# v7-flex2811_long.net
KiCad netlist of a schematic drawn in EAGLE
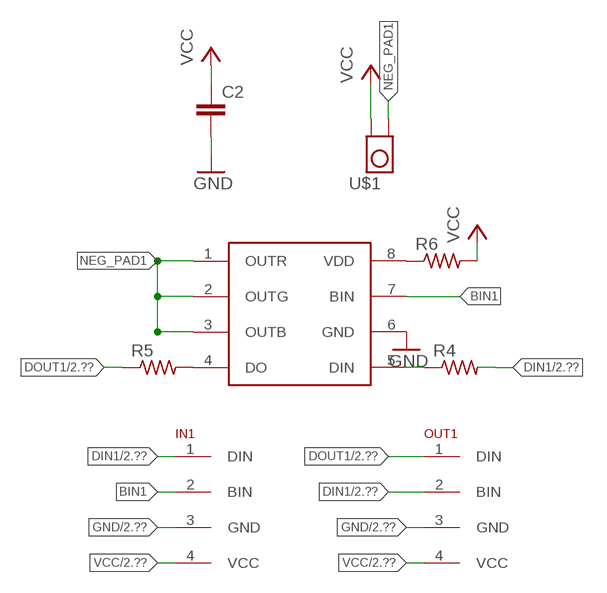
[diagram p0: schematic, sheet 1]
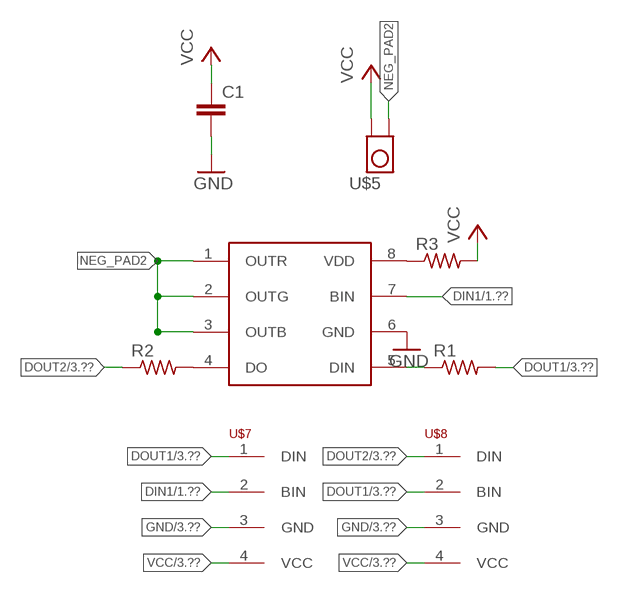
[diagram p1: schematic, sheet 2]
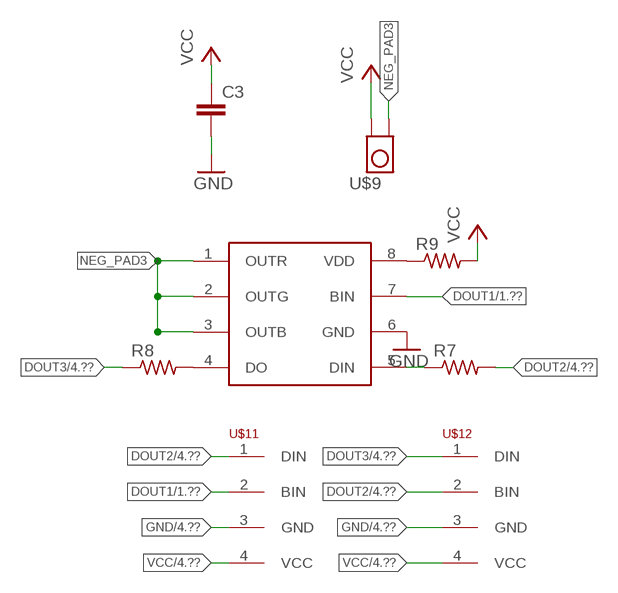
[diagram p2: schematic, sheet 3]
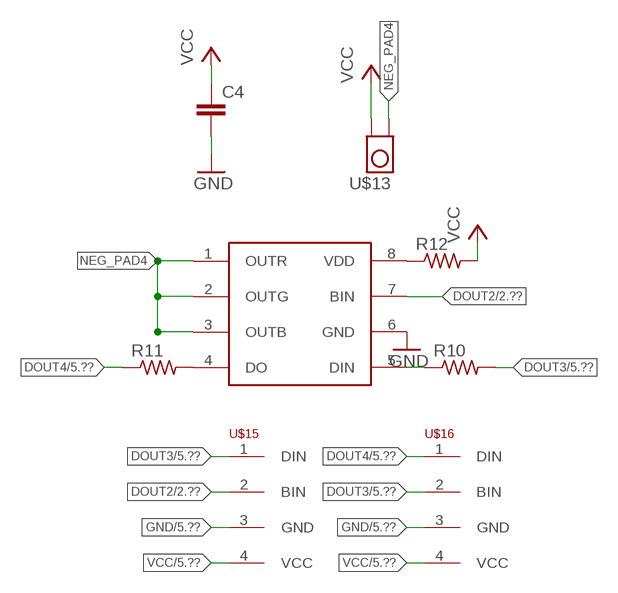
[diagram p3: schematic, sheet 4]
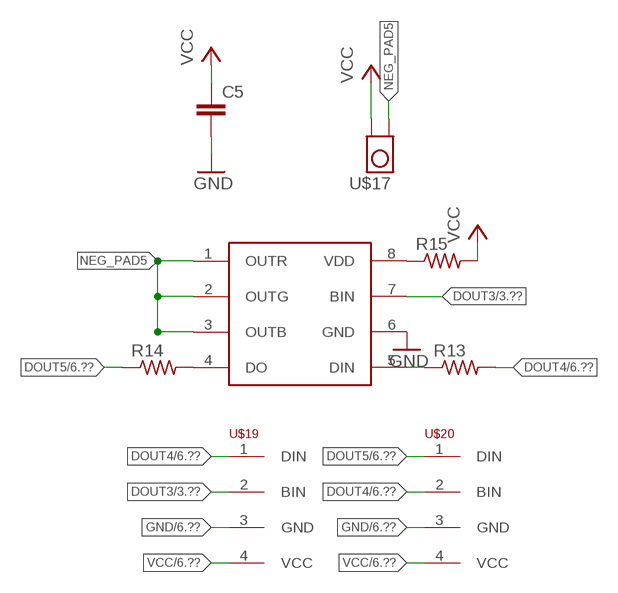
[diagram p4: schematic, sheet 5]
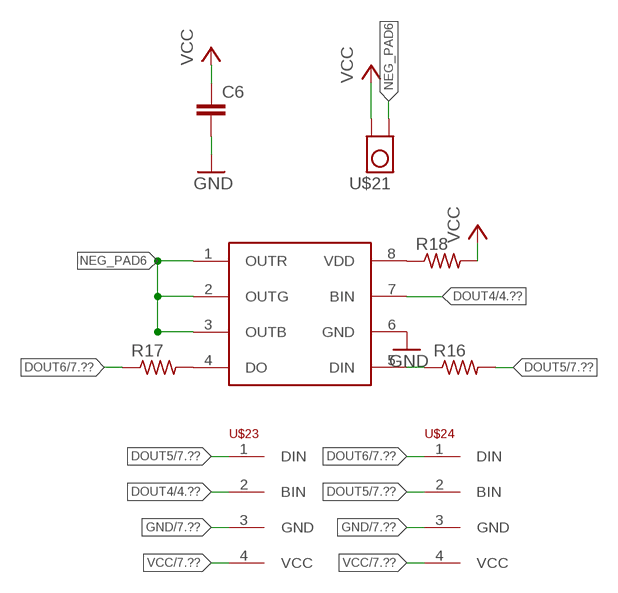
[diagram p5: schematic, sheet 6]
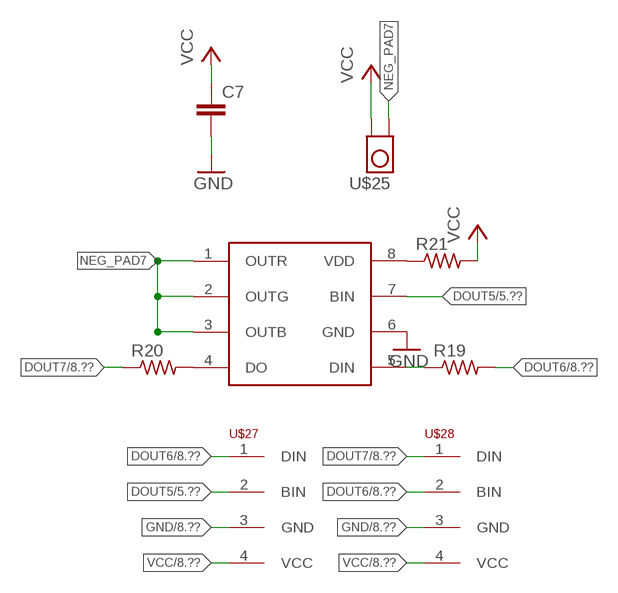
[diagram p6: schematic, sheet 7]
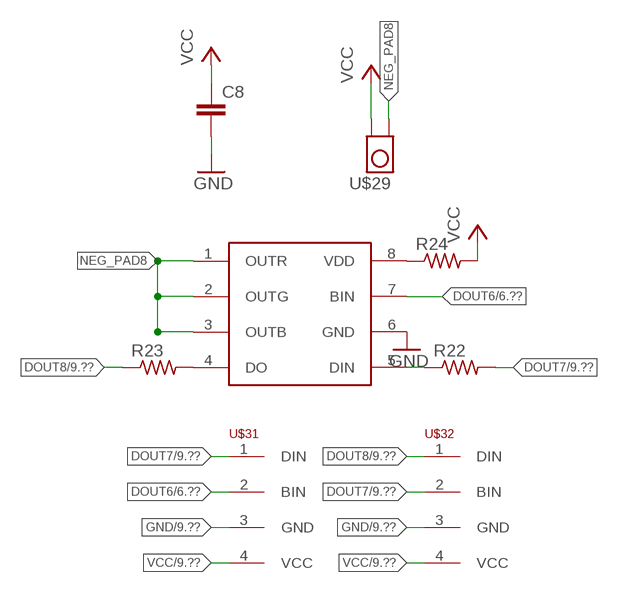
[diagram p7: schematic, sheet 8]
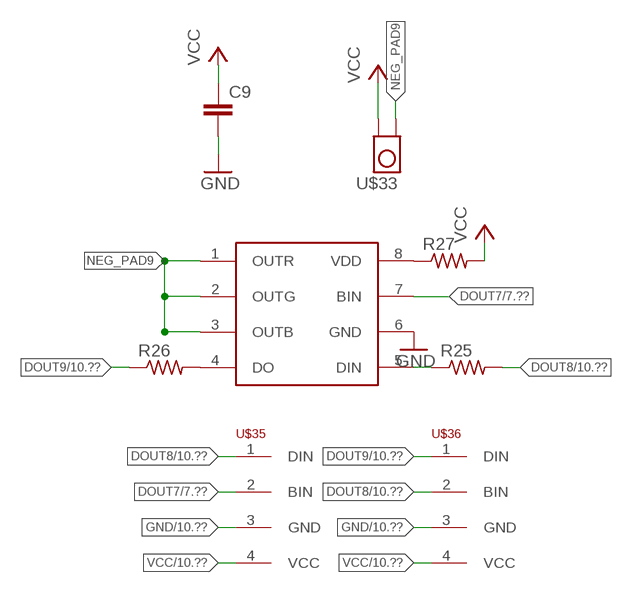
[diagram p8: schematic, sheet 9]
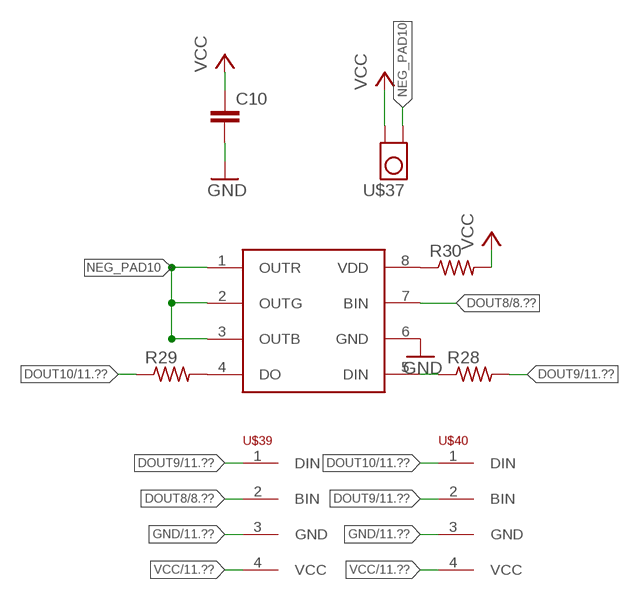
[diagram p9: schematic, sheet 10]
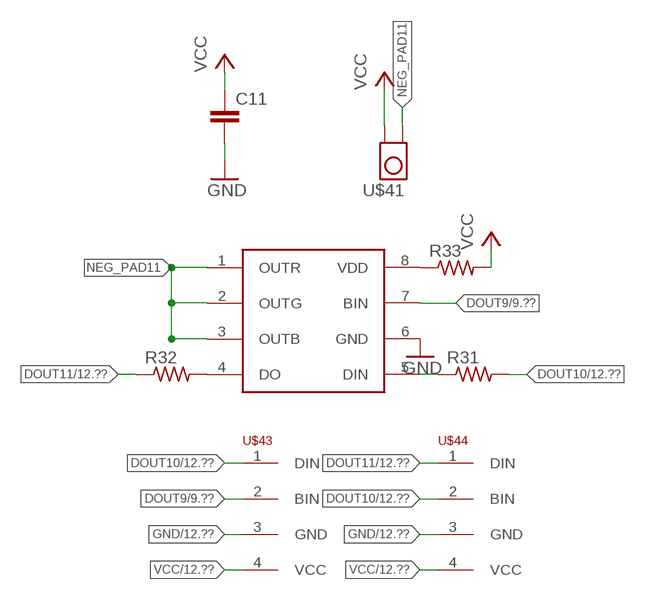
[diagram p10: schematic, sheet 11]
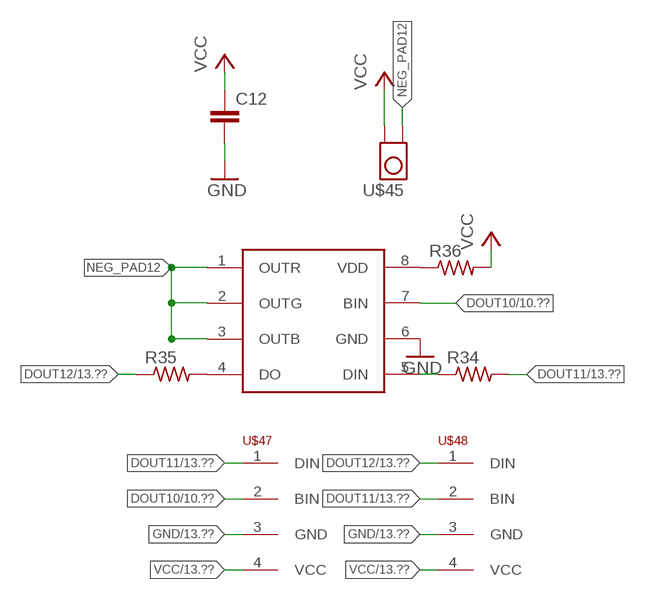
[diagram p11: schematic, sheet 12]
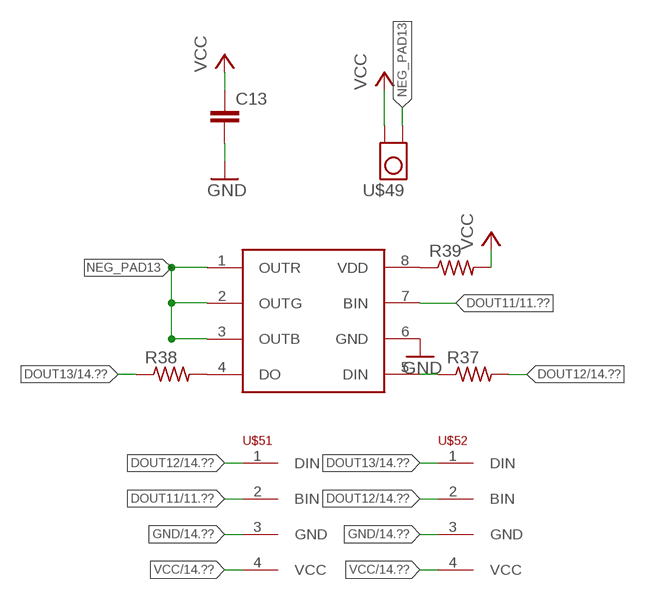
[diagram p12: schematic, sheet 13]
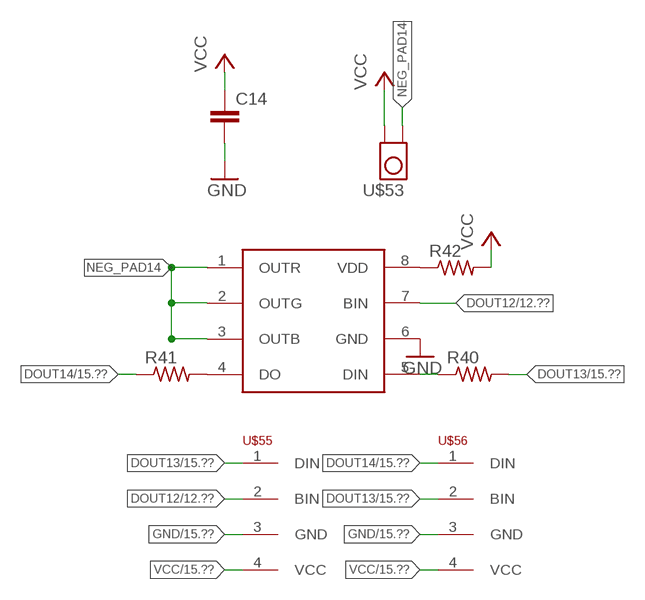
[diagram p13: schematic, sheet 14]
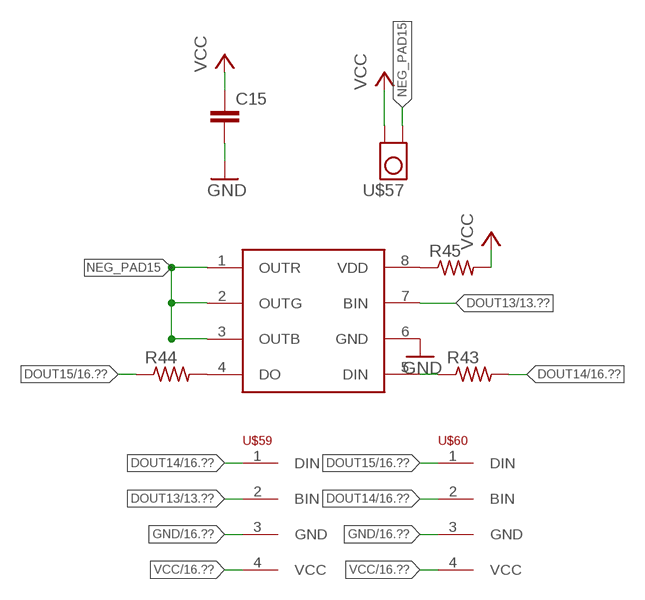
[diagram p14: schematic, sheet 15]
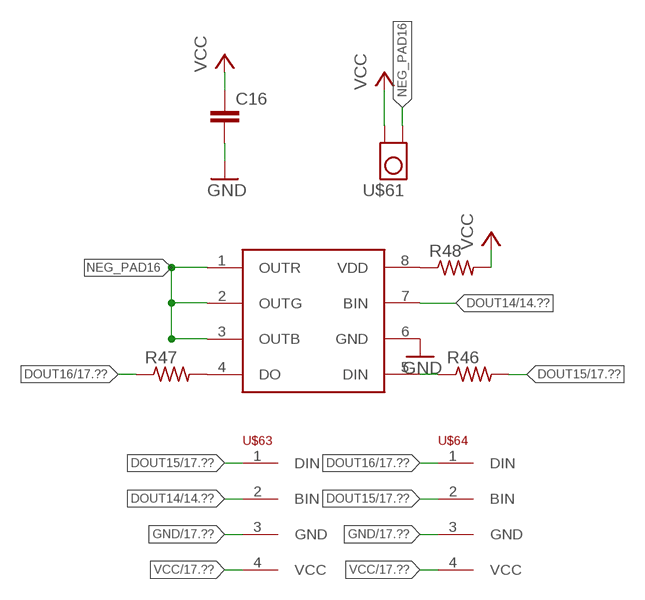
[diagram p15: schematic, sheet 16]
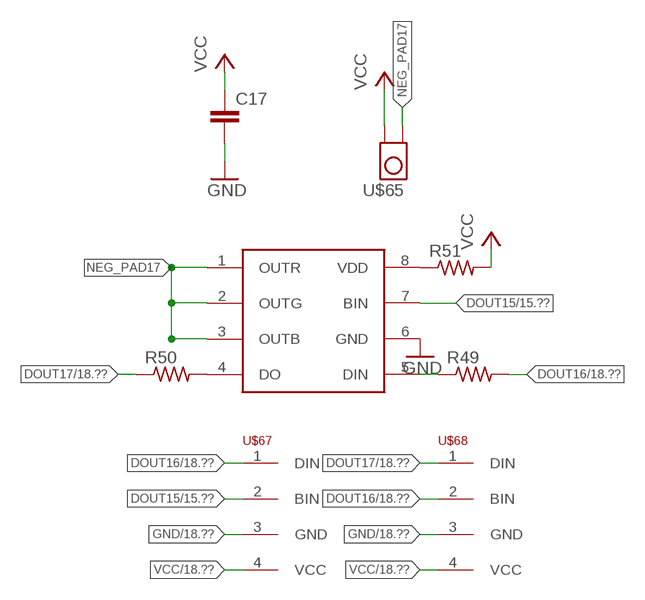
[diagram p16: schematic, sheet 17]
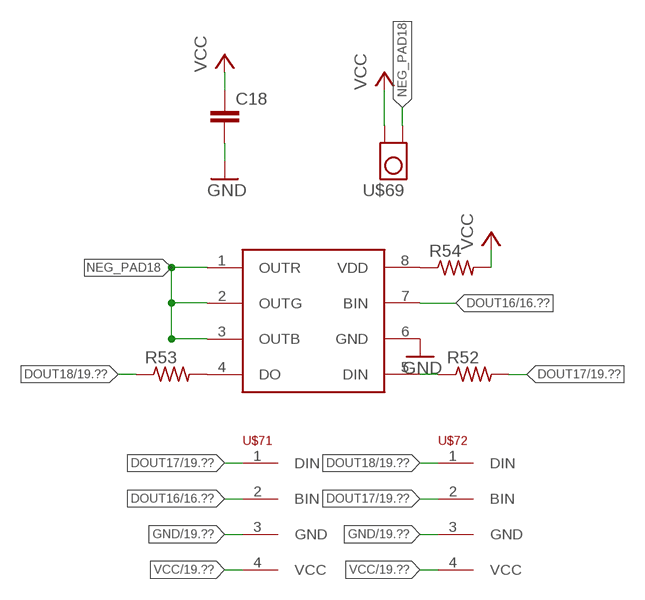
[diagram p17: schematic, sheet 18]
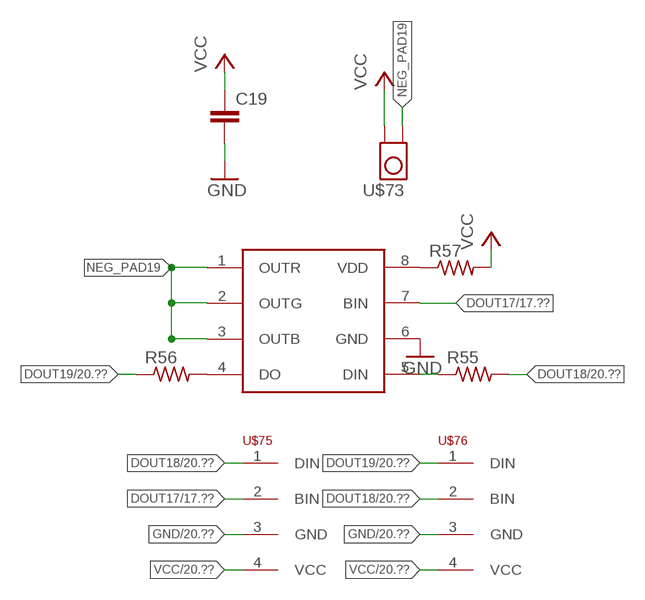
[diagram p18: schematic, sheet 19]
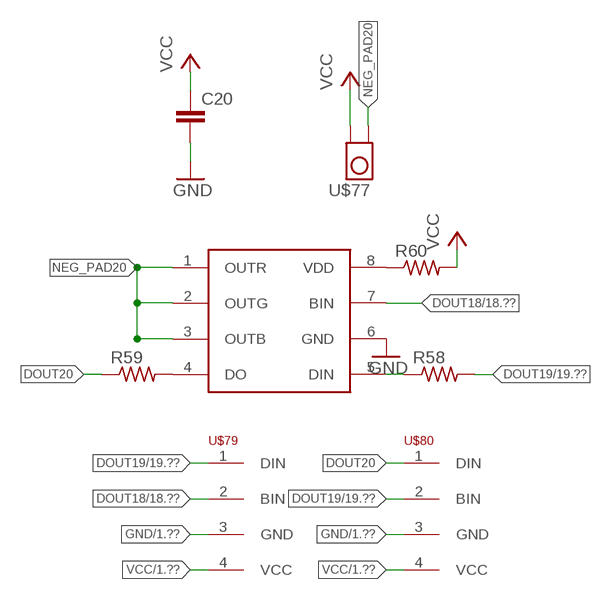
[diagram p19: schematic, sheet 20]

(export (version "E")
  (design (tool "Eeschema 10.0.6"))
  (components
    (comp (ref "C18")
      (value "C-EUC0201")
      (footprint "eagle-import:C0201")
      (libsource (lib "eagle-import") (part "C-EUC0201"))
    )
    (comp (ref "R52")
      (value "R-US_R0201")
      (footprint "eagle-import:R0201")
      (libsource (lib "eagle-import") (part "R-US_R0201"))
    )
    (comp (ref "R53")
      (value "R-US_R0201")
      (footprint "eagle-import:R0201")
      (libsource (lib "eagle-import") (part "R-US_R0201"))
    )
    (comp (ref "R54")
      (value "R-US_R0201")
      (footprint "eagle-import:R0201")
      (libsource (lib "eagle-import") (part "R-US_R0201"))
    )
    (comp (ref "U$69")
      (value "TP_4MM_MED_PAD")
      (footprint "eagle-import:TP_4MM_MED_PAD")
      (libsource (lib "eagle-import") (part "TP_4MM_MED_PAD"))
    )
    (comp (ref "U$70")
      (value "WS2818")
      (footprint "eagle-import:SO08")
      (libsource (lib "eagle-import") (part "WS2818"))
    )
    (comp (ref "U$71")
      (value "4PAD")
      (footprint "eagle-import:4PAD")
      (libsource (lib "eagle-import") (part "4PAD"))
    )
    (comp (ref "U$72")
      (value "4PAD")
      (footprint "eagle-import:4PAD")
      (libsource (lib "eagle-import") (part "4PAD"))
    )
    (comp (ref "C12")
      (value "C-EUC0201")
      (footprint "eagle-import:C0201")
      (libsource (lib "eagle-import") (part "C-EUC0201"))
    )
    (comp (ref "R34")
      (value "R-US_R0201")
      (footprint "eagle-import:R0201")
      (libsource (lib "eagle-import") (part "R-US_R0201"))
    )
    (comp (ref "R35")
      (value "R-US_R0201")
      (footprint "eagle-import:R0201")
      (libsource (lib "eagle-import") (part "R-US_R0201"))
    )
    (comp (ref "R36")
      (value "R-US_R0201")
      (footprint "eagle-import:R0201")
      (libsource (lib "eagle-import") (part "R-US_R0201"))
    )
    (comp (ref "U$45")
      (value "TP_4MM_MED_PAD")
      (footprint "eagle-import:TP_4MM_MED_PAD")
      (libsource (lib "eagle-import") (part "TP_4MM_MED_PAD"))
    )
    (comp (ref "U$46")
      (value "WS2818")
      (footprint "eagle-import:SO08")
      (libsource (lib "eagle-import") (part "WS2818"))
    )
    (comp (ref "U$47")
      (value "4PAD")
      (footprint "eagle-import:4PAD")
      (libsource (lib "eagle-import") (part "4PAD"))
    )
    (comp (ref "U$48")
      (value "4PAD")
      (footprint "eagle-import:4PAD")
      (libsource (lib "eagle-import") (part "4PAD"))
    )
    (comp (ref "C8")
      (value "C-EUC0201")
      (footprint "eagle-import:C0201")
      (libsource (lib "eagle-import") (part "C-EUC0201"))
    )
    (comp (ref "R22")
      (value "R-US_R0201")
      (footprint "eagle-import:R0201")
      (libsource (lib "eagle-import") (part "R-US_R0201"))
    )
    (comp (ref "R23")
      (value "R-US_R0201")
      (footprint "eagle-import:R0201")
      (libsource (lib "eagle-import") (part "R-US_R0201"))
    )
    (comp (ref "R24")
      (value "R-US_R0201")
      (footprint "eagle-import:R0201")
      (libsource (lib "eagle-import") (part "R-US_R0201"))
    )
    (comp (ref "U$29")
      (value "TP_4MM_MED_PAD")
      (footprint "eagle-import:TP_4MM_MED_PAD")
      (libsource (lib "eagle-import") (part "TP_4MM_MED_PAD"))
    )
    (comp (ref "U$30")
      (value "WS2818")
      (footprint "eagle-import:SO08")
      (libsource (lib "eagle-import") (part "WS2818"))
    )
    (comp (ref "U$31")
      (value "4PAD")
      (footprint "eagle-import:4PAD")
      (libsource (lib "eagle-import") (part "4PAD"))
    )
    (comp (ref "U$32")
      (value "4PAD")
      (footprint "eagle-import:4PAD")
      (libsource (lib "eagle-import") (part "4PAD"))
    )
    (comp (ref "C14")
      (value "C-EUC0201")
      (footprint "eagle-import:C0201")
      (libsource (lib "eagle-import") (part "C-EUC0201"))
    )
    (comp (ref "R40")
      (value "R-US_R0201")
      (footprint "eagle-import:R0201")
      (libsource (lib "eagle-import") (part "R-US_R0201"))
    )
    (comp (ref "R41")
      (value "R-US_R0201")
      (footprint "eagle-import:R0201")
      (libsource (lib "eagle-import") (part "R-US_R0201"))
    )
    (comp (ref "R42")
      (value "R-US_R0201")
      (footprint "eagle-import:R0201")
      (libsource (lib "eagle-import") (part "R-US_R0201"))
    )
    (comp (ref "U$53")
      (value "TP_4MM_MED_PAD")
      (footprint "eagle-import:TP_4MM_MED_PAD")
      (libsource (lib "eagle-import") (part "TP_4MM_MED_PAD"))
    )
    (comp (ref "U$54")
      (value "WS2818")
      (footprint "eagle-import:SO08")
      (libsource (lib "eagle-import") (part "WS2818"))
    )
    (comp (ref "U$55")
      (value "4PAD")
      (footprint "eagle-import:4PAD")
      (libsource (lib "eagle-import") (part "4PAD"))
    )
    (comp (ref "U$56")
      (value "4PAD")
      (footprint "eagle-import:4PAD")
      (libsource (lib "eagle-import") (part "4PAD"))
    )
    (comp (ref "C4")
      (value "C-EUC0201")
      (footprint "eagle-import:C0201")
      (libsource (lib "eagle-import") (part "C-EUC0201"))
    )
    (comp (ref "R10")
      (value "R-US_R0201")
      (footprint "eagle-import:R0201")
      (libsource (lib "eagle-import") (part "R-US_R0201"))
    )
    (comp (ref "R11")
      (value "R-US_R0201")
      (footprint "eagle-import:R0201")
      (libsource (lib "eagle-import") (part "R-US_R0201"))
    )
    (comp (ref "R12")
      (value "R-US_R0201")
      (footprint "eagle-import:R0201")
      (libsource (lib "eagle-import") (part "R-US_R0201"))
    )
    (comp (ref "U$13")
      (value "TP_4MM_MED_PAD")
      (footprint "eagle-import:TP_4MM_MED_PAD")
      (libsource (lib "eagle-import") (part "TP_4MM_MED_PAD"))
    )
    (comp (ref "U$14")
      (value "WS2818")
      (footprint "eagle-import:SO08")
      (libsource (lib "eagle-import") (part "WS2818"))
    )
    (comp (ref "U$15")
      (value "4PAD")
      (footprint "eagle-import:4PAD")
      (libsource (lib "eagle-import") (part "4PAD"))
    )
    (comp (ref "U$16")
      (value "4PAD")
      (footprint "eagle-import:4PAD")
      (libsource (lib "eagle-import") (part "4PAD"))
    )
    (comp (ref "C7")
      (value "C-EUC0201")
      (footprint "eagle-import:C0201")
      (libsource (lib "eagle-import") (part "C-EUC0201"))
    )
    (comp (ref "R19")
      (value "R-US_R0201")
      (footprint "eagle-import:R0201")
      (libsource (lib "eagle-import") (part "R-US_R0201"))
    )
    (comp (ref "R20")
      (value "R-US_R0201")
      (footprint "eagle-import:R0201")
      (libsource (lib "eagle-import") (part "R-US_R0201"))
    )
    (comp (ref "R21")
      (value "R-US_R0201")
      (footprint "eagle-import:R0201")
      (libsource (lib "eagle-import") (part "R-US_R0201"))
    )
    (comp (ref "U$25")
      (value "TP_4MM_MED_PAD")
      (footprint "eagle-import:TP_4MM_MED_PAD")
      (libsource (lib "eagle-import") (part "TP_4MM_MED_PAD"))
    )
    (comp (ref "U$26")
      (value "WS2818")
      (footprint "eagle-import:SO08")
      (libsource (lib "eagle-import") (part "WS2818"))
    )
    (comp (ref "U$27")
      (value "4PAD")
      (footprint "eagle-import:4PAD")
      (libsource (lib "eagle-import") (part "4PAD"))
    )
    (comp (ref "U$28")
      (value "4PAD")
      (footprint "eagle-import:4PAD")
      (libsource (lib "eagle-import") (part "4PAD"))
    )
    (comp (ref "C9")
      (value "C-EUC0201")
      (footprint "eagle-import:C0201")
      (libsource (lib "eagle-import") (part "C-EUC0201"))
    )
    (comp (ref "R25")
      (value "R-US_R0201")
      (footprint "eagle-import:R0201")
      (libsource (lib "eagle-import") (part "R-US_R0201"))
    )
    (comp (ref "R26")
      (value "R-US_R0201")
      (footprint "eagle-import:R0201")
      (libsource (lib "eagle-import") (part "R-US_R0201"))
    )
    (comp (ref "R27")
      (value "R-US_R0201")
      (footprint "eagle-import:R0201")
      (libsource (lib "eagle-import") (part "R-US_R0201"))
    )
    (comp (ref "U$33")
      (value "TP_4MM_MED_PAD")
      (footprint "eagle-import:TP_4MM_MED_PAD")
      (libsource (lib "eagle-import") (part "TP_4MM_MED_PAD"))
    )
    (comp (ref "U$34")
      (value "WS2818")
      (footprint "eagle-import:SO08")
      (libsource (lib "eagle-import") (part "WS2818"))
    )
    (comp (ref "U$35")
      (value "4PAD")
      (footprint "eagle-import:4PAD")
      (libsource (lib "eagle-import") (part "4PAD"))
    )
    (comp (ref "U$36")
      (value "4PAD")
      (footprint "eagle-import:4PAD")
      (libsource (lib "eagle-import") (part "4PAD"))
    )
    (comp (ref "C10")
      (value "C-EUC0201")
      (footprint "eagle-import:C0201")
      (libsource (lib "eagle-import") (part "C-EUC0201"))
    )
    (comp (ref "R28")
      (value "R-US_R0201")
      (footprint "eagle-import:R0201")
      (libsource (lib "eagle-import") (part "R-US_R0201"))
    )
    (comp (ref "R29")
      (value "R-US_R0201")
      (footprint "eagle-import:R0201")
      (libsource (lib "eagle-import") (part "R-US_R0201"))
    )
    (comp (ref "R30")
      (value "R-US_R0201")
      (footprint "eagle-import:R0201")
      (libsource (lib "eagle-import") (part "R-US_R0201"))
    )
    (comp (ref "U$37")
      (value "TP_4MM_MED_PAD")
      (footprint "eagle-import:TP_4MM_MED_PAD")
      (libsource (lib "eagle-import") (part "TP_4MM_MED_PAD"))
    )
    (comp (ref "U$38")
      (value "WS2818")
      (footprint "eagle-import:SO08")
      (libsource (lib "eagle-import") (part "WS2818"))
    )
    (comp (ref "U$39")
      (value "4PAD")
      (footprint "eagle-import:4PAD")
      (libsource (lib "eagle-import") (part "4PAD"))
    )
    (comp (ref "U$40")
      (value "4PAD")
      (footprint "eagle-import:4PAD")
      (libsource (lib "eagle-import") (part "4PAD"))
    )
    (comp (ref "C11")
      (value "C-EUC0201")
      (footprint "eagle-import:C0201")
      (libsource (lib "eagle-import") (part "C-EUC0201"))
    )
    (comp (ref "R31")
      (value "R-US_R0201")
      (footprint "eagle-import:R0201")
      (libsource (lib "eagle-import") (part "R-US_R0201"))
    )
    (comp (ref "R32")
      (value "R-US_R0201")
      (footprint "eagle-import:R0201")
      (libsource (lib "eagle-import") (part "R-US_R0201"))
    )
    (comp (ref "R33")
      (value "R-US_R0201")
      (footprint "eagle-import:R0201")
      (libsource (lib "eagle-import") (part "R-US_R0201"))
    )
    (comp (ref "U$41")
      (value "TP_4MM_MED_PAD")
      (footprint "eagle-import:TP_4MM_MED_PAD")
      (libsource (lib "eagle-import") (part "TP_4MM_MED_PAD"))
    )
    (comp (ref "U$42")
      (value "WS2818")
      (footprint "eagle-import:SO08")
      (libsource (lib "eagle-import") (part "WS2818"))
    )
    (comp (ref "U$43")
      (value "4PAD")
      (footprint "eagle-import:4PAD")
      (libsource (lib "eagle-import") (part "4PAD"))
    )
    (comp (ref "U$44")
      (value "4PAD")
      (footprint "eagle-import:4PAD")
      (libsource (lib "eagle-import") (part "4PAD"))
    )
    (comp (ref "C19")
      (value "C-EUC0201")
      (footprint "eagle-import:C0201")
      (libsource (lib "eagle-import") (part "C-EUC0201"))
    )
    (comp (ref "R55")
      (value "R-US_R0201")
      (footprint "eagle-import:R0201")
      (libsource (lib "eagle-import") (part "R-US_R0201"))
    )
    (comp (ref "R56")
      (value "R-US_R0201")
      (footprint "eagle-import:R0201")
      (libsource (lib "eagle-import") (part "R-US_R0201"))
    )
    (comp (ref "R57")
      (value "R-US_R0201")
      (footprint "eagle-import:R0201")
      (libsource (lib "eagle-import") (part "R-US_R0201"))
    )
    (comp (ref "U$73")
      (value "TP_4MM_MED_PAD")
      (footprint "eagle-import:TP_4MM_MED_PAD")
      (libsource (lib "eagle-import") (part "TP_4MM_MED_PAD"))
    )
    (comp (ref "U$74")
      (value "WS2818")
      (footprint "eagle-import:SO08")
      (libsource (lib "eagle-import") (part "WS2818"))
    )
    (comp (ref "U$75")
      (value "4PAD")
      (footprint "eagle-import:4PAD")
      (libsource (lib "eagle-import") (part "4PAD"))
    )
    (comp (ref "U$76")
      (value "4PAD")
      (footprint "eagle-import:4PAD")
      (libsource (lib "eagle-import") (part "4PAD"))
    )
    (comp (ref "C15")
      (value "C-EUC0201")
      (footprint "eagle-import:C0201")
      (libsource (lib "eagle-import") (part "C-EUC0201"))
    )
    (comp (ref "R43")
      (value "R-US_R0201")
      (footprint "eagle-import:R0201")
      (libsource (lib "eagle-import") (part "R-US_R0201"))
    )
    (comp (ref "R44")
      (value "R-US_R0201")
      (footprint "eagle-import:R0201")
      (libsource (lib "eagle-import") (part "R-US_R0201"))
    )
    (comp (ref "R45")
      (value "R-US_R0201")
      (footprint "eagle-import:R0201")
      (libsource (lib "eagle-import") (part "R-US_R0201"))
    )
    (comp (ref "U$57")
      (value "TP_4MM_MED_PAD")
      (footprint "eagle-import:TP_4MM_MED_PAD")
      (libsource (lib "eagle-import") (part "TP_4MM_MED_PAD"))
    )
    (comp (ref "U$58")
      (value "WS2818")
      (footprint "eagle-import:SO08")
      (libsource (lib "eagle-import") (part "WS2818"))
    )
    (comp (ref "U$59")
      (value "4PAD")
      (footprint "eagle-import:4PAD")
      (libsource (lib "eagle-import") (part "4PAD"))
    )
    (comp (ref "U$60")
      (value "4PAD")
      (footprint "eagle-import:4PAD")
      (libsource (lib "eagle-import") (part "4PAD"))
    )
    (comp (ref "C5")
      (value "C-EUC0201")
      (footprint "eagle-import:C0201")
      (libsource (lib "eagle-import") (part "C-EUC0201"))
    )
    (comp (ref "R13")
      (value "R-US_R0201")
      (footprint "eagle-import:R0201")
      (libsource (lib "eagle-import") (part "R-US_R0201"))
    )
    (comp (ref "R14")
      (value "R-US_R0201")
      (footprint "eagle-import:R0201")
      (libsource (lib "eagle-import") (part "R-US_R0201"))
    )
    (comp (ref "R15")
      (value "R-US_R0201")
      (footprint "eagle-import:R0201")
      (libsource (lib "eagle-import") (part "R-US_R0201"))
    )
    (comp (ref "U$17")
      (value "TP_4MM_MED_PAD")
      (footprint "eagle-import:TP_4MM_MED_PAD")
      (libsource (lib "eagle-import") (part "TP_4MM_MED_PAD"))
    )
    (comp (ref "U$18")
      (value "WS2818")
      (footprint "eagle-import:SO08")
      (libsource (lib "eagle-import") (part "WS2818"))
    )
    (comp (ref "U$19")
      (value "4PAD")
      (footprint "eagle-import:4PAD")
      (libsource (lib "eagle-import") (part "4PAD"))
    )
    (comp (ref "U$20")
      (value "4PAD")
      (footprint "eagle-import:4PAD")
      (libsource (lib "eagle-import") (part "4PAD"))
    )
    (comp (ref "C20")
      (value "C-EUC0201")
      (footprint "eagle-import:C0201")
      (libsource (lib "eagle-import") (part "C-EUC0201"))
    )
    (comp (ref "R58")
      (value "R-US_R0201")
      (footprint "eagle-import:R0201")
      (libsource (lib "eagle-import") (part "R-US_R0201"))
    )
    (comp (ref "R59")
      (value "R-US_R0201")
      (footprint "eagle-import:R0201")
      (libsource (lib "eagle-import") (part "R-US_R0201"))
    )
    (comp (ref "R60")
      (value "R-US_R0201")
      (footprint "eagle-import:R0201")
      (libsource (lib "eagle-import") (part "R-US_R0201"))
    )
    (comp (ref "U$77")
      (value "TP_4MM_MED_PAD")
      (footprint "eagle-import:TP_4MM_MED_PAD")
      (libsource (lib "eagle-import") (part "TP_4MM_MED_PAD"))
    )
    (comp (ref "U$78")
      (value "WS2818")
      (footprint "eagle-import:SO08")
      (libsource (lib "eagle-import") (part "WS2818"))
    )
    (comp (ref "U$79")
      (value "4PAD")
      (footprint "eagle-import:4PAD")
      (libsource (lib "eagle-import") (part "4PAD"))
    )
    (comp (ref "U$80")
      (value "4PAD")
      (footprint "eagle-import:4PAD")
      (libsource (lib "eagle-import") (part "4PAD"))
    )
    (comp (ref "C17")
      (value "C-EUC0201")
      (footprint "eagle-import:C0201")
      (libsource (lib "eagle-import") (part "C-EUC0201"))
    )
    (comp (ref "R49")
      (value "R-US_R0201")
      (footprint "eagle-import:R0201")
      (libsource (lib "eagle-import") (part "R-US_R0201"))
    )
    (comp (ref "R50")
      (value "R-US_R0201")
      (footprint "eagle-import:R0201")
      (libsource (lib "eagle-import") (part "R-US_R0201"))
    )
    (comp (ref "R51")
      (value "R-US_R0201")
      (footprint "eagle-import:R0201")
      (libsource (lib "eagle-import") (part "R-US_R0201"))
    )
    (comp (ref "U$65")
      (value "TP_4MM_MED_PAD")
      (footprint "eagle-import:TP_4MM_MED_PAD")
      (libsource (lib "eagle-import") (part "TP_4MM_MED_PAD"))
    )
    (comp (ref "U$66")
      (value "WS2818")
      (footprint "eagle-import:SO08")
      (libsource (lib "eagle-import") (part "WS2818"))
    )
    (comp (ref "U$67")
      (value "4PAD")
      (footprint "eagle-import:4PAD")
      (libsource (lib "eagle-import") (part "4PAD"))
    )
    (comp (ref "U$68")
      (value "4PAD")
      (footprint "eagle-import:4PAD")
      (libsource (lib "eagle-import") (part "4PAD"))
    )
    (comp (ref "C6")
      (value "C-EUC0201")
      (footprint "eagle-import:C0201")
      (libsource (lib "eagle-import") (part "C-EUC0201"))
    )
    (comp (ref "R16")
      (value "R-US_R0201")
      (footprint "eagle-import:R0201")
      (libsource (lib "eagle-import") (part "R-US_R0201"))
    )
    (comp (ref "R17")
      (value "R-US_R0201")
      (footprint "eagle-import:R0201")
      (libsource (lib "eagle-import") (part "R-US_R0201"))
    )
    (comp (ref "R18")
      (value "R-US_R0201")
      (footprint "eagle-import:R0201")
      (libsource (lib "eagle-import") (part "R-US_R0201"))
    )
    (comp (ref "U$21")
      (value "TP_4MM_MED_PAD")
      (footprint "eagle-import:TP_4MM_MED_PAD")
      (libsource (lib "eagle-import") (part "TP_4MM_MED_PAD"))
    )
    (comp (ref "U$22")
      (value "WS2818")
      (footprint "eagle-import:SO08")
      (libsource (lib "eagle-import") (part "WS2818"))
    )
    (comp (ref "U$23")
      (value "4PAD")
      (footprint "eagle-import:4PAD")
      (libsource (lib "eagle-import") (part "4PAD"))
    )
    (comp (ref "U$24")
      (value "4PAD")
      (footprint "eagle-import:4PAD")
      (libsource (lib "eagle-import") (part "4PAD"))
    )
    (comp (ref "C2")
      (value "C-EUC0201")
      (footprint "eagle-import:C0201")
      (libsource (lib "eagle-import") (part "C-EUC0201"))
    )
    (comp (ref "IN1")
      (value "4PAD")
      (footprint "eagle-import:4PAD")
      (libsource (lib "eagle-import") (part "4PAD"))
    )
    (comp (ref "OUT1")
      (value "4PAD")
      (footprint "eagle-import:4PAD")
      (libsource (lib "eagle-import") (part "4PAD"))
    )
    (comp (ref "R4")
      (value "R-US_R0201")
      (footprint "eagle-import:R0201")
      (libsource (lib "eagle-import") (part "R-US_R0201"))
    )
    (comp (ref "R5")
      (value "R-US_R0201")
      (footprint "eagle-import:R0201")
      (libsource (lib "eagle-import") (part "R-US_R0201"))
    )
    (comp (ref "R6")
      (value "R-US_R0201")
      (footprint "eagle-import:R0201")
      (libsource (lib "eagle-import") (part "R-US_R0201"))
    )
    (comp (ref "U$1")
      (value "TP_4MM_MED_PAD")
      (footprint "eagle-import:TP_4MM_MED_PAD")
      (libsource (lib "eagle-import") (part "TP_4MM_MED_PAD"))
    )
    (comp (ref "U$2")
      (value "WS2818")
      (footprint "eagle-import:SO08")
      (libsource (lib "eagle-import") (part "WS2818"))
    )
    (comp (ref "C13")
      (value "C-EUC0201")
      (footprint "eagle-import:C0201")
      (libsource (lib "eagle-import") (part "C-EUC0201"))
    )
    (comp (ref "R37")
      (value "R-US_R0201")
      (footprint "eagle-import:R0201")
      (libsource (lib "eagle-import") (part "R-US_R0201"))
    )
    (comp (ref "R38")
      (value "R-US_R0201")
      (footprint "eagle-import:R0201")
      (libsource (lib "eagle-import") (part "R-US_R0201"))
    )
    (comp (ref "R39")
      (value "R-US_R0201")
      (footprint "eagle-import:R0201")
      (libsource (lib "eagle-import") (part "R-US_R0201"))
    )
    (comp (ref "U$49")
      (value "TP_4MM_MED_PAD")
      (footprint "eagle-import:TP_4MM_MED_PAD")
      (libsource (lib "eagle-import") (part "TP_4MM_MED_PAD"))
    )
    (comp (ref "U$50")
      (value "WS2818")
      (footprint "eagle-import:SO08")
      (libsource (lib "eagle-import") (part "WS2818"))
    )
    (comp (ref "U$51")
      (value "4PAD")
      (footprint "eagle-import:4PAD")
      (libsource (lib "eagle-import") (part "4PAD"))
    )
    (comp (ref "U$52")
      (value "4PAD")
      (footprint "eagle-import:4PAD")
      (libsource (lib "eagle-import") (part "4PAD"))
    )
    (comp (ref "C16")
      (value "C-EUC0201")
      (footprint "eagle-import:C0201")
      (libsource (lib "eagle-import") (part "C-EUC0201"))
    )
    (comp (ref "R46")
      (value "R-US_R0201")
      (footprint "eagle-import:R0201")
      (libsource (lib "eagle-import") (part "R-US_R0201"))
    )
    (comp (ref "R47")
      (value "R-US_R0201")
      (footprint "eagle-import:R0201")
      (libsource (lib "eagle-import") (part "R-US_R0201"))
    )
    (comp (ref "R48")
      (value "R-US_R0201")
      (footprint "eagle-import:R0201")
      (libsource (lib "eagle-import") (part "R-US_R0201"))
    )
    (comp (ref "U$61")
      (value "TP_4MM_MED_PAD")
      (footprint "eagle-import:TP_4MM_MED_PAD")
      (libsource (lib "eagle-import") (part "TP_4MM_MED_PAD"))
    )
    (comp (ref "U$62")
      (value "WS2818")
      (footprint "eagle-import:SO08")
      (libsource (lib "eagle-import") (part "WS2818"))
    )
    (comp (ref "U$63")
      (value "4PAD")
      (footprint "eagle-import:4PAD")
      (libsource (lib "eagle-import") (part "4PAD"))
    )
    (comp (ref "U$64")
      (value "4PAD")
      (footprint "eagle-import:4PAD")
      (libsource (lib "eagle-import") (part "4PAD"))
    )
    (comp (ref "C3")
      (value "C-EUC0201")
      (footprint "eagle-import:C0201")
      (libsource (lib "eagle-import") (part "C-EUC0201"))
    )
    (comp (ref "R7")
      (value "R-US_R0201")
      (footprint "eagle-import:R0201")
      (libsource (lib "eagle-import") (part "R-US_R0201"))
    )
    (comp (ref "R8")
      (value "R-US_R0201")
      (footprint "eagle-import:R0201")
      (libsource (lib "eagle-import") (part "R-US_R0201"))
    )
    (comp (ref "R9")
      (value "R-US_R0201")
      (footprint "eagle-import:R0201")
      (libsource (lib "eagle-import") (part "R-US_R0201"))
    )
    (comp (ref "U$9")
      (value "TP_4MM_MED_PAD")
      (footprint "eagle-import:TP_4MM_MED_PAD")
      (libsource (lib "eagle-import") (part "TP_4MM_MED_PAD"))
    )
    (comp (ref "U$10")
      (value "WS2818")
      (footprint "eagle-import:SO08")
      (libsource (lib "eagle-import") (part "WS2818"))
    )
    (comp (ref "U$11")
      (value "4PAD")
      (footprint "eagle-import:4PAD")
      (libsource (lib "eagle-import") (part "4PAD"))
    )
    (comp (ref "U$12")
      (value "4PAD")
      (footprint "eagle-import:4PAD")
      (libsource (lib "eagle-import") (part "4PAD"))
    )
    (comp (ref "C1")
      (value "C-EUC0201")
      (footprint "eagle-import:C0201")
      (libsource (lib "eagle-import") (part "C-EUC0201"))
    )
    (comp (ref "R1")
      (value "R-US_R0201")
      (footprint "eagle-import:R0201")
      (libsource (lib "eagle-import") (part "R-US_R0201"))
    )
    (comp (ref "R2")
      (value "R-US_R0201")
      (footprint "eagle-import:R0201")
      (libsource (lib "eagle-import") (part "R-US_R0201"))
    )
    (comp (ref "R3")
      (value "R-US_R0201")
      (footprint "eagle-import:R0201")
      (libsource (lib "eagle-import") (part "R-US_R0201"))
    )
    (comp (ref "U$5")
      (value "TP_4MM_MED_PAD")
      (footprint "eagle-import:TP_4MM_MED_PAD")
      (libsource (lib "eagle-import") (part "TP_4MM_MED_PAD"))
    )
    (comp (ref "U$6")
      (value "WS2818")
      (footprint "eagle-import:SO08")
      (libsource (lib "eagle-import") (part "WS2818"))
    )
    (comp (ref "U$7")
      (value "4PAD")
      (footprint "eagle-import:4PAD")
      (libsource (lib "eagle-import") (part "4PAD"))
    )
    (comp (ref "U$8")
      (value "4PAD")
      (footprint "eagle-import:4PAD")
      (libsource (lib "eagle-import") (part "4PAD"))
    )
  )
  (nets
    (net (code "1") (name "BIN1") (class "Default")
      (node (ref "IN1") (pin "2") (pinfunction "BIN_2") (pintype "bidirectional"))
      (node (ref "U$2") (pin "7") (pinfunction "BIN_7") (pintype "bidirectional"))
    )
    (net (code "2") (name "DIN1") (class "Default")
      (node (ref "IN1") (pin "1") (pinfunction "DIN_1") (pintype "bidirectional"))
      (node (ref "OUT1") (pin "2") (pinfunction "BIN_2") (pintype "bidirectional"))
      (node (ref "R4") (pin "2") (pinfunction "2_2") (pintype "passive"))
      (node (ref "U$6") (pin "7") (pinfunction "BIN_7") (pintype "bidirectional"))
      (node (ref "U$7") (pin "2") (pinfunction "BIN_2") (pintype "bidirectional"))
    )
    (net (code "3") (name "DOUT1") (class "Default")
      (node (ref "OUT1") (pin "1") (pinfunction "DIN_1") (pintype "bidirectional"))
      (node (ref "R1") (pin "2") (pinfunction "2_2") (pintype "passive"))
      (node (ref "R5") (pin "1") (pinfunction "1_1") (pintype "passive"))
      (node (ref "U$10") (pin "7") (pinfunction "BIN_7") (pintype "bidirectional"))
      (node (ref "U$11") (pin "2") (pinfunction "BIN_2") (pintype "bidirectional"))
      (node (ref "U$7") (pin "1") (pinfunction "DIN_1") (pintype "bidirectional"))
      (node (ref "U$8") (pin "2") (pinfunction "BIN_2") (pintype "bidirectional"))
    )
    (net (code "4") (name "DOUT2") (class "Default")
      (node (ref "R2") (pin "1") (pinfunction "1_1") (pintype "passive"))
      (node (ref "R7") (pin "2") (pinfunction "2_2") (pintype "passive"))
      (node (ref "U$11") (pin "1") (pinfunction "DIN_1") (pintype "bidirectional"))
      (node (ref "U$12") (pin "2") (pinfunction "BIN_2") (pintype "bidirectional"))
      (node (ref "U$14") (pin "7") (pinfunction "BIN_7") (pintype "bidirectional"))
      (node (ref "U$15") (pin "2") (pinfunction "BIN_2") (pintype "bidirectional"))
      (node (ref "U$8") (pin "1") (pinfunction "DIN_1") (pintype "bidirectional"))
    )
    (net (code "5") (name "DOUT3") (class "Default")
      (node (ref "R10") (pin "2") (pinfunction "2_2") (pintype "passive"))
      (node (ref "R8") (pin "1") (pinfunction "1_1") (pintype "passive"))
      (node (ref "U$12") (pin "1") (pinfunction "DIN_1") (pintype "bidirectional"))
      (node (ref "U$15") (pin "1") (pinfunction "DIN_1") (pintype "bidirectional"))
      (node (ref "U$16") (pin "2") (pinfunction "BIN_2") (pintype "bidirectional"))
      (node (ref "U$18") (pin "7") (pinfunction "BIN_7") (pintype "bidirectional"))
      (node (ref "U$19") (pin "2") (pinfunction "BIN_2") (pintype "bidirectional"))
    )
    (net (code "6") (name "DOUT4") (class "Default")
      (node (ref "R11") (pin "1") (pinfunction "1_1") (pintype "passive"))
      (node (ref "R13") (pin "2") (pinfunction "2_2") (pintype "passive"))
      (node (ref "U$16") (pin "1") (pinfunction "DIN_1") (pintype "bidirectional"))
      (node (ref "U$19") (pin "1") (pinfunction "DIN_1") (pintype "bidirectional"))
      (node (ref "U$20") (pin "2") (pinfunction "BIN_2") (pintype "bidirectional"))
      (node (ref "U$22") (pin "7") (pinfunction "BIN_7") (pintype "bidirectional"))
      (node (ref "U$23") (pin "2") (pinfunction "BIN_2") (pintype "bidirectional"))
    )
    (net (code "7") (name "DOUT5") (class "Default")
      (node (ref "R14") (pin "1") (pinfunction "1_1") (pintype "passive"))
      (node (ref "R16") (pin "2") (pinfunction "2_2") (pintype "passive"))
      (node (ref "U$20") (pin "1") (pinfunction "DIN_1") (pintype "bidirectional"))
      (node (ref "U$23") (pin "1") (pinfunction "DIN_1") (pintype "bidirectional"))
      (node (ref "U$24") (pin "2") (pinfunction "BIN_2") (pintype "bidirectional"))
      (node (ref "U$26") (pin "7") (pinfunction "BIN_7") (pintype "bidirectional"))
      (node (ref "U$27") (pin "2") (pinfunction "BIN_2") (pintype "bidirectional"))
    )
    (net (code "8") (name "DOUT6") (class "Default")
      (node (ref "R17") (pin "1") (pinfunction "1_1") (pintype "passive"))
      (node (ref "R19") (pin "2") (pinfunction "2_2") (pintype "passive"))
      (node (ref "U$24") (pin "1") (pinfunction "DIN_1") (pintype "bidirectional"))
      (node (ref "U$27") (pin "1") (pinfunction "DIN_1") (pintype "bidirectional"))
      (node (ref "U$28") (pin "2") (pinfunction "BIN_2") (pintype "bidirectional"))
      (node (ref "U$30") (pin "7") (pinfunction "BIN_7") (pintype "bidirectional"))
      (node (ref "U$31") (pin "2") (pinfunction "BIN_2") (pintype "bidirectional"))
    )
    (net (code "9") (name "DOUT7") (class "Default")
      (node (ref "R20") (pin "1") (pinfunction "1_1") (pintype "passive"))
      (node (ref "R22") (pin "2") (pinfunction "2_2") (pintype "passive"))
      (node (ref "U$28") (pin "1") (pinfunction "DIN_1") (pintype "bidirectional"))
      (node (ref "U$31") (pin "1") (pinfunction "DIN_1") (pintype "bidirectional"))
      (node (ref "U$32") (pin "2") (pinfunction "BIN_2") (pintype "bidirectional"))
      (node (ref "U$34") (pin "7") (pinfunction "BIN_7") (pintype "bidirectional"))
      (node (ref "U$35") (pin "2") (pinfunction "BIN_2") (pintype "bidirectional"))
    )
    (net (code "10") (name "DOUT8") (class "Default")
      (node (ref "R23") (pin "1") (pinfunction "1_1") (pintype "passive"))
      (node (ref "R25") (pin "2") (pinfunction "2_2") (pintype "passive"))
      (node (ref "U$32") (pin "1") (pinfunction "DIN_1") (pintype "bidirectional"))
      (node (ref "U$35") (pin "1") (pinfunction "DIN_1") (pintype "bidirectional"))
      (node (ref "U$36") (pin "2") (pinfunction "BIN_2") (pintype "bidirectional"))
      (node (ref "U$38") (pin "7") (pinfunction "BIN_7") (pintype "bidirectional"))
      (node (ref "U$39") (pin "2") (pinfunction "BIN_2") (pintype "bidirectional"))
    )
    (net (code "11") (name "DOUT9") (class "Default")
      (node (ref "R26") (pin "1") (pinfunction "1_1") (pintype "passive"))
      (node (ref "R28") (pin "2") (pinfunction "2_2") (pintype "passive"))
      (node (ref "U$36") (pin "1") (pinfunction "DIN_1") (pintype "bidirectional"))
      (node (ref "U$39") (pin "1") (pinfunction "DIN_1") (pintype "bidirectional"))
      (node (ref "U$40") (pin "2") (pinfunction "BIN_2") (pintype "bidirectional"))
      (node (ref "U$42") (pin "7") (pinfunction "BIN_7") (pintype "bidirectional"))
      (node (ref "U$43") (pin "2") (pinfunction "BIN_2") (pintype "bidirectional"))
    )
    (net (code "12") (name "DOUT10") (class "Default")
      (node (ref "R29") (pin "1") (pinfunction "1_1") (pintype "passive"))
      (node (ref "R31") (pin "2") (pinfunction "2_2") (pintype "passive"))
      (node (ref "U$40") (pin "1") (pinfunction "DIN_1") (pintype "bidirectional"))
      (node (ref "U$43") (pin "1") (pinfunction "DIN_1") (pintype "bidirectional"))
      (node (ref "U$44") (pin "2") (pinfunction "BIN_2") (pintype "bidirectional"))
      (node (ref "U$46") (pin "7") (pinfunction "BIN_7") (pintype "bidirectional"))
      (node (ref "U$47") (pin "2") (pinfunction "BIN_2") (pintype "bidirectional"))
    )
    (net (code "13") (name "DOUT11") (class "Default")
      (node (ref "R32") (pin "1") (pinfunction "1_1") (pintype "passive"))
      (node (ref "R34") (pin "2") (pinfunction "2_2") (pintype "passive"))
      (node (ref "U$44") (pin "1") (pinfunction "DIN_1") (pintype "bidirectional"))
      (node (ref "U$47") (pin "1") (pinfunction "DIN_1") (pintype "bidirectional"))
      (node (ref "U$48") (pin "2") (pinfunction "BIN_2") (pintype "bidirectional"))
      (node (ref "U$50") (pin "7") (pinfunction "BIN_7") (pintype "bidirectional"))
      (node (ref "U$51") (pin "2") (pinfunction "BIN_2") (pintype "bidirectional"))
    )
    (net (code "14") (name "DOUT12") (class "Default")
      (node (ref "R35") (pin "1") (pinfunction "1_1") (pintype "passive"))
      (node (ref "R37") (pin "2") (pinfunction "2_2") (pintype "passive"))
      (node (ref "U$48") (pin "1") (pinfunction "DIN_1") (pintype "bidirectional"))
      (node (ref "U$51") (pin "1") (pinfunction "DIN_1") (pintype "bidirectional"))
      (node (ref "U$52") (pin "2") (pinfunction "BIN_2") (pintype "bidirectional"))
      (node (ref "U$54") (pin "7") (pinfunction "BIN_7") (pintype "bidirectional"))
      (node (ref "U$55") (pin "2") (pinfunction "BIN_2") (pintype "bidirectional"))
    )
    (net (code "15") (name "DOUT13") (class "Default")
      (node (ref "R38") (pin "1") (pinfunction "1_1") (pintype "passive"))
      (node (ref "R40") (pin "2") (pinfunction "2_2") (pintype "passive"))
      (node (ref "U$52") (pin "1") (pinfunction "DIN_1") (pintype "bidirectional"))
      (node (ref "U$55") (pin "1") (pinfunction "DIN_1") (pintype "bidirectional"))
      (node (ref "U$56") (pin "2") (pinfunction "BIN_2") (pintype "bidirectional"))
      (node (ref "U$58") (pin "7") (pinfunction "BIN_7") (pintype "bidirectional"))
      (node (ref "U$59") (pin "2") (pinfunction "BIN_2") (pintype "bidirectional"))
    )
    (net (code "16") (name "DOUT14") (class "Default")
      (node (ref "R41") (pin "1") (pinfunction "1_1") (pintype "passive"))
      (node (ref "R43") (pin "2") (pinfunction "2_2") (pintype "passive"))
      (node (ref "U$56") (pin "1") (pinfunction "DIN_1") (pintype "bidirectional"))
      (node (ref "U$59") (pin "1") (pinfunction "DIN_1") (pintype "bidirectional"))
      (node (ref "U$60") (pin "2") (pinfunction "BIN_2") (pintype "bidirectional"))
      (node (ref "U$62") (pin "7") (pinfunction "BIN_7") (pintype "bidirectional"))
      (node (ref "U$63") (pin "2") (pinfunction "BIN_2") (pintype "bidirectional"))
    )
    (net (code "17") (name "DOUT15") (class "Default")
      (node (ref "R44") (pin "1") (pinfunction "1_1") (pintype "passive"))
      (node (ref "R46") (pin "2") (pinfunction "2_2") (pintype "passive"))
      (node (ref "U$60") (pin "1") (pinfunction "DIN_1") (pintype "bidirectional"))
      (node (ref "U$63") (pin "1") (pinfunction "DIN_1") (pintype "bidirectional"))
      (node (ref "U$64") (pin "2") (pinfunction "BIN_2") (pintype "bidirectional"))
      (node (ref "U$66") (pin "7") (pinfunction "BIN_7") (pintype "bidirectional"))
      (node (ref "U$67") (pin "2") (pinfunction "BIN_2") (pintype "bidirectional"))
    )
    (net (code "18") (name "DOUT16") (class "Default")
      (node (ref "R47") (pin "1") (pinfunction "1_1") (pintype "passive"))
      (node (ref "R49") (pin "2") (pinfunction "2_2") (pintype "passive"))
      (node (ref "U$64") (pin "1") (pinfunction "DIN_1") (pintype "bidirectional"))
      (node (ref "U$67") (pin "1") (pinfunction "DIN_1") (pintype "bidirectional"))
      (node (ref "U$68") (pin "2") (pinfunction "BIN_2") (pintype "bidirectional"))
      (node (ref "U$70") (pin "7") (pinfunction "BIN_7") (pintype "bidirectional"))
      (node (ref "U$71") (pin "2") (pinfunction "BIN_2") (pintype "bidirectional"))
    )
    (net (code "19") (name "DOUT17") (class "Default")
      (node (ref "R50") (pin "1") (pinfunction "1_1") (pintype "passive"))
      (node (ref "R52") (pin "2") (pinfunction "2_2") (pintype "passive"))
      (node (ref "U$68") (pin "1") (pinfunction "DIN_1") (pintype "bidirectional"))
      (node (ref "U$71") (pin "1") (pinfunction "DIN_1") (pintype "bidirectional"))
      (node (ref "U$72") (pin "2") (pinfunction "BIN_2") (pintype "bidirectional"))
      (node (ref "U$74") (pin "7") (pinfunction "BIN_7") (pintype "bidirectional"))
      (node (ref "U$75") (pin "2") (pinfunction "BIN_2") (pintype "bidirectional"))
    )
    (net (code "20") (name "DOUT18") (class "Default")
      (node (ref "R53") (pin "1") (pinfunction "1_1") (pintype "passive"))
      (node (ref "R55") (pin "2") (pinfunction "2_2") (pintype "passive"))
      (node (ref "U$72") (pin "1") (pinfunction "DIN_1") (pintype "bidirectional"))
      (node (ref "U$75") (pin "1") (pinfunction "DIN_1") (pintype "bidirectional"))
      (node (ref "U$76") (pin "2") (pinfunction "BIN_2") (pintype "bidirectional"))
      (node (ref "U$78") (pin "7") (pinfunction "BIN_7") (pintype "bidirectional"))
      (node (ref "U$79") (pin "2") (pinfunction "BIN_2") (pintype "bidirectional"))
    )
    (net (code "21") (name "DOUT19") (class "Default")
      (node (ref "R56") (pin "1") (pinfunction "1_1") (pintype "passive"))
      (node (ref "R58") (pin "2") (pinfunction "2_2") (pintype "passive"))
      (node (ref "U$76") (pin "1") (pinfunction "DIN_1") (pintype "bidirectional"))
      (node (ref "U$79") (pin "1") (pinfunction "DIN_1") (pintype "bidirectional"))
      (node (ref "U$80") (pin "2") (pinfunction "BIN_2") (pintype "bidirectional"))
    )
    (net (code "22") (name "DOUT20") (class "Default")
      (node (ref "R59") (pin "1") (pinfunction "1_1") (pintype "passive"))
      (node (ref "U$80") (pin "1") (pinfunction "DIN_1") (pintype "bidirectional"))
    )
    (net (code "23") (name "GND") (class "Default")
      (node (ref "C1") (pin "2") (pinfunction "2_2") (pintype "passive"))
      (node (ref "C10") (pin "2") (pinfunction "2_2") (pintype "passive"))
      (node (ref "C11") (pin "2") (pinfunction "2_2") (pintype "passive"))
      (node (ref "C12") (pin "2") (pinfunction "2_2") (pintype "passive"))
      (node (ref "C13") (pin "2") (pinfunction "2_2") (pintype "passive"))
      (node (ref "C14") (pin "2") (pinfunction "2_2") (pintype "passive"))
      (node (ref "C15") (pin "2") (pinfunction "2_2") (pintype "passive"))
      (node (ref "C16") (pin "2") (pinfunction "2_2") (pintype "passive"))
      (node (ref "C17") (pin "2") (pinfunction "2_2") (pintype "passive"))
      (node (ref "C18") (pin "2") (pinfunction "2_2") (pintype "passive"))
      (node (ref "C19") (pin "2") (pinfunction "2_2") (pintype "passive"))
      (node (ref "C2") (pin "2") (pinfunction "2_2") (pintype "passive"))
      (node (ref "C20") (pin "2") (pinfunction "2_2") (pintype "passive"))
      (node (ref "C3") (pin "2") (pinfunction "2_2") (pintype "passive"))
      (node (ref "C4") (pin "2") (pinfunction "2_2") (pintype "passive"))
      (node (ref "C5") (pin "2") (pinfunction "2_2") (pintype "passive"))
      (node (ref "C6") (pin "2") (pinfunction "2_2") (pintype "passive"))
      (node (ref "C7") (pin "2") (pinfunction "2_2") (pintype "passive"))
      (node (ref "C8") (pin "2") (pinfunction "2_2") (pintype "passive"))
      (node (ref "C9") (pin "2") (pinfunction "2_2") (pintype "passive"))
      (node (ref "IN1") (pin "3") (pinfunction "GND_3") (pintype "bidirectional"))
      (node (ref "OUT1") (pin "3") (pinfunction "GND_3") (pintype "bidirectional"))
      (node (ref "U$10") (pin "6") (pinfunction "GND_6") (pintype "bidirectional"))
      (node (ref "U$11") (pin "3") (pinfunction "GND_3") (pintype "bidirectional"))
      (node (ref "U$12") (pin "3") (pinfunction "GND_3") (pintype "bidirectional"))
      (node (ref "U$14") (pin "6") (pinfunction "GND_6") (pintype "bidirectional"))
      (node (ref "U$15") (pin "3") (pinfunction "GND_3") (pintype "bidirectional"))
      (node (ref "U$16") (pin "3") (pinfunction "GND_3") (pintype "bidirectional"))
      (node (ref "U$18") (pin "6") (pinfunction "GND_6") (pintype "bidirectional"))
      (node (ref "U$19") (pin "3") (pinfunction "GND_3") (pintype "bidirectional"))
      (node (ref "U$2") (pin "6") (pinfunction "GND_6") (pintype "bidirectional"))
      (node (ref "U$20") (pin "3") (pinfunction "GND_3") (pintype "bidirectional"))
      (node (ref "U$22") (pin "6") (pinfunction "GND_6") (pintype "bidirectional"))
      (node (ref "U$23") (pin "3") (pinfunction "GND_3") (pintype "bidirectional"))
      (node (ref "U$24") (pin "3") (pinfunction "GND_3") (pintype "bidirectional"))
      (node (ref "U$26") (pin "6") (pinfunction "GND_6") (pintype "bidirectional"))
      (node (ref "U$27") (pin "3") (pinfunction "GND_3") (pintype "bidirectional"))
      (node (ref "U$28") (pin "3") (pinfunction "GND_3") (pintype "bidirectional"))
      (node (ref "U$30") (pin "6") (pinfunction "GND_6") (pintype "bidirectional"))
      (node (ref "U$31") (pin "3") (pinfunction "GND_3") (pintype "bidirectional"))
      (node (ref "U$32") (pin "3") (pinfunction "GND_3") (pintype "bidirectional"))
      (node (ref "U$34") (pin "6") (pinfunction "GND_6") (pintype "bidirectional"))
      (node (ref "U$35") (pin "3") (pinfunction "GND_3") (pintype "bidirectional"))
      (node (ref "U$36") (pin "3") (pinfunction "GND_3") (pintype "bidirectional"))
      (node (ref "U$38") (pin "6") (pinfunction "GND_6") (pintype "bidirectional"))
      (node (ref "U$39") (pin "3") (pinfunction "GND_3") (pintype "bidirectional"))
      (node (ref "U$40") (pin "3") (pinfunction "GND_3") (pintype "bidirectional"))
      (node (ref "U$42") (pin "6") (pinfunction "GND_6") (pintype "bidirectional"))
      (node (ref "U$43") (pin "3") (pinfunction "GND_3") (pintype "bidirectional"))
      (node (ref "U$44") (pin "3") (pinfunction "GND_3") (pintype "bidirectional"))
      (node (ref "U$46") (pin "6") (pinfunction "GND_6") (pintype "bidirectional"))
      (node (ref "U$47") (pin "3") (pinfunction "GND_3") (pintype "bidirectional"))
      (node (ref "U$48") (pin "3") (pinfunction "GND_3") (pintype "bidirectional"))
      (node (ref "U$50") (pin "6") (pinfunction "GND_6") (pintype "bidirectional"))
      (node (ref "U$51") (pin "3") (pinfunction "GND_3") (pintype "bidirectional"))
      (node (ref "U$52") (pin "3") (pinfunction "GND_3") (pintype "bidirectional"))
      (node (ref "U$54") (pin "6") (pinfunction "GND_6") (pintype "bidirectional"))
      (node (ref "U$55") (pin "3") (pinfunction "GND_3") (pintype "bidirectional"))
      (node (ref "U$56") (pin "3") (pinfunction "GND_3") (pintype "bidirectional"))
      (node (ref "U$58") (pin "6") (pinfunction "GND_6") (pintype "bidirectional"))
      (node (ref "U$59") (pin "3") (pinfunction "GND_3") (pintype "bidirectional"))
      (node (ref "U$6") (pin "6") (pinfunction "GND_6") (pintype "bidirectional"))
      (node (ref "U$60") (pin "3") (pinfunction "GND_3") (pintype "bidirectional"))
      (node (ref "U$62") (pin "6") (pinfunction "GND_6") (pintype "bidirectional"))
      (node (ref "U$63") (pin "3") (pinfunction "GND_3") (pintype "bidirectional"))
      (node (ref "U$64") (pin "3") (pinfunction "GND_3") (pintype "bidirectional"))
      (node (ref "U$66") (pin "6") (pinfunction "GND_6") (pintype "bidirectional"))
      (node (ref "U$67") (pin "3") (pinfunction "GND_3") (pintype "bidirectional"))
      (node (ref "U$68") (pin "3") (pinfunction "GND_3") (pintype "bidirectional"))
      (node (ref "U$7") (pin "3") (pinfunction "GND_3") (pintype "bidirectional"))
      (node (ref "U$70") (pin "6") (pinfunction "GND_6") (pintype "bidirectional"))
      (node (ref "U$71") (pin "3") (pinfunction "GND_3") (pintype "bidirectional"))
      (node (ref "U$72") (pin "3") (pinfunction "GND_3") (pintype "bidirectional"))
      (node (ref "U$74") (pin "6") (pinfunction "GND_6") (pintype "bidirectional"))
      (node (ref "U$75") (pin "3") (pinfunction "GND_3") (pintype "bidirectional"))
      (node (ref "U$76") (pin "3") (pinfunction "GND_3") (pintype "bidirectional"))
      (node (ref "U$78") (pin "6") (pinfunction "GND_6") (pintype "bidirectional"))
      (node (ref "U$79") (pin "3") (pinfunction "GND_3") (pintype "bidirectional"))
      (node (ref "U$8") (pin "3") (pinfunction "GND_3") (pintype "bidirectional"))
      (node (ref "U$80") (pin "3") (pinfunction "GND_3") (pintype "bidirectional"))
    )
    (net (code "24") (name "NEG_PAD1") (class "Default")
      (node (ref "U$1") (pin "P$1") (pinfunction "0_P$1") (pintype "bidirectional"))
      (node (ref "U$2") (pin "1") (pinfunction "OUTR_1") (pintype "bidirectional"))
      (node (ref "U$2") (pin "2") (pinfunction "OUTG_2") (pintype "bidirectional"))
      (node (ref "U$2") (pin "3") (pinfunction "OUTB_3") (pintype "bidirectional"))
    )
    (net (code "25") (name "NEG_PAD2") (class "Default")
      (node (ref "U$5") (pin "P$1") (pinfunction "0_P$1") (pintype "bidirectional"))
      (node (ref "U$6") (pin "1") (pinfunction "OUTR_1") (pintype "bidirectional"))
      (node (ref "U$6") (pin "2") (pinfunction "OUTG_2") (pintype "bidirectional"))
      (node (ref "U$6") (pin "3") (pinfunction "OUTB_3") (pintype "bidirectional"))
    )
    (net (code "26") (name "NEG_PAD3") (class "Default")
      (node (ref "U$10") (pin "1") (pinfunction "OUTR_1") (pintype "bidirectional"))
      (node (ref "U$10") (pin "2") (pinfunction "OUTG_2") (pintype "bidirectional"))
      (node (ref "U$10") (pin "3") (pinfunction "OUTB_3") (pintype "bidirectional"))
      (node (ref "U$9") (pin "P$1") (pinfunction "0_P$1") (pintype "bidirectional"))
    )
    (net (code "27") (name "NEG_PAD4") (class "Default")
      (node (ref "U$13") (pin "P$1") (pinfunction "0_P$1") (pintype "bidirectional"))
      (node (ref "U$14") (pin "1") (pinfunction "OUTR_1") (pintype "bidirectional"))
      (node (ref "U$14") (pin "2") (pinfunction "OUTG_2") (pintype "bidirectional"))
      (node (ref "U$14") (pin "3") (pinfunction "OUTB_3") (pintype "bidirectional"))
    )
    (net (code "28") (name "NEG_PAD5") (class "Default")
      (node (ref "U$17") (pin "P$1") (pinfunction "0_P$1") (pintype "bidirectional"))
      (node (ref "U$18") (pin "1") (pinfunction "OUTR_1") (pintype "bidirectional"))
      (node (ref "U$18") (pin "2") (pinfunction "OUTG_2") (pintype "bidirectional"))
      (node (ref "U$18") (pin "3") (pinfunction "OUTB_3") (pintype "bidirectional"))
    )
    (net (code "29") (name "NEG_PAD6") (class "Default")
      (node (ref "U$21") (pin "P$1") (pinfunction "0_P$1") (pintype "bidirectional"))
      (node (ref "U$22") (pin "1") (pinfunction "OUTR_1") (pintype "bidirectional"))
      (node (ref "U$22") (pin "2") (pinfunction "OUTG_2") (pintype "bidirectional"))
      (node (ref "U$22") (pin "3") (pinfunction "OUTB_3") (pintype "bidirectional"))
    )
    (net (code "30") (name "NEG_PAD7") (class "Default")
      (node (ref "U$25") (pin "P$1") (pinfunction "0_P$1") (pintype "bidirectional"))
      (node (ref "U$26") (pin "1") (pinfunction "OUTR_1") (pintype "bidirectional"))
      (node (ref "U$26") (pin "2") (pinfunction "OUTG_2") (pintype "bidirectional"))
      (node (ref "U$26") (pin "3") (pinfunction "OUTB_3") (pintype "bidirectional"))
    )
    (net (code "31") (name "NEG_PAD8") (class "Default")
      (node (ref "U$29") (pin "P$1") (pinfunction "0_P$1") (pintype "bidirectional"))
      (node (ref "U$30") (pin "1") (pinfunction "OUTR_1") (pintype "bidirectional"))
      (node (ref "U$30") (pin "2") (pinfunction "OUTG_2") (pintype "bidirectional"))
      (node (ref "U$30") (pin "3") (pinfunction "OUTB_3") (pintype "bidirectional"))
    )
    (net (code "32") (name "NEG_PAD9") (class "Default")
      (node (ref "U$33") (pin "P$1") (pinfunction "0_P$1") (pintype "bidirectional"))
      (node (ref "U$34") (pin "1") (pinfunction "OUTR_1") (pintype "bidirectional"))
      (node (ref "U$34") (pin "2") (pinfunction "OUTG_2") (pintype "bidirectional"))
      (node (ref "U$34") (pin "3") (pinfunction "OUTB_3") (pintype "bidirectional"))
    )
    (net (code "33") (name "NEG_PAD10") (class "Default")
      (node (ref "U$37") (pin "P$1") (pinfunction "0_P$1") (pintype "bidirectional"))
      (node (ref "U$38") (pin "1") (pinfunction "OUTR_1") (pintype "bidirectional"))
      (node (ref "U$38") (pin "2") (pinfunction "OUTG_2") (pintype "bidirectional"))
      (node (ref "U$38") (pin "3") (pinfunction "OUTB_3") (pintype "bidirectional"))
    )
    (net (code "34") (name "NEG_PAD11") (class "Default")
      (node (ref "U$41") (pin "P$1") (pinfunction "0_P$1") (pintype "bidirectional"))
      (node (ref "U$42") (pin "1") (pinfunction "OUTR_1") (pintype "bidirectional"))
      (node (ref "U$42") (pin "2") (pinfunction "OUTG_2") (pintype "bidirectional"))
      (node (ref "U$42") (pin "3") (pinfunction "OUTB_3") (pintype "bidirectional"))
    )
    (net (code "35") (name "NEG_PAD12") (class "Default")
      (node (ref "U$45") (pin "P$1") (pinfunction "0_P$1") (pintype "bidirectional"))
      (node (ref "U$46") (pin "1") (pinfunction "OUTR_1") (pintype "bidirectional"))
      (node (ref "U$46") (pin "2") (pinfunction "OUTG_2") (pintype "bidirectional"))
      (node (ref "U$46") (pin "3") (pinfunction "OUTB_3") (pintype "bidirectional"))
    )
    (net (code "36") (name "NEG_PAD13") (class "Default")
      (node (ref "U$49") (pin "P$1") (pinfunction "0_P$1") (pintype "bidirectional"))
      (node (ref "U$50") (pin "1") (pinfunction "OUTR_1") (pintype "bidirectional"))
      (node (ref "U$50") (pin "2") (pinfunction "OUTG_2") (pintype "bidirectional"))
      (node (ref "U$50") (pin "3") (pinfunction "OUTB_3") (pintype "bidirectional"))
    )
    (net (code "37") (name "NEG_PAD14") (class "Default")
      (node (ref "U$53") (pin "P$1") (pinfunction "0_P$1") (pintype "bidirectional"))
      (node (ref "U$54") (pin "1") (pinfunction "OUTR_1") (pintype "bidirectional"))
      (node (ref "U$54") (pin "2") (pinfunction "OUTG_2") (pintype "bidirectional"))
      (node (ref "U$54") (pin "3") (pinfunction "OUTB_3") (pintype "bidirectional"))
    )
    (net (code "38") (name "NEG_PAD15") (class "Default")
      (node (ref "U$57") (pin "P$1") (pinfunction "0_P$1") (pintype "bidirectional"))
      (node (ref "U$58") (pin "1") (pinfunction "OUTR_1") (pintype "bidirectional"))
      (node (ref "U$58") (pin "2") (pinfunction "OUTG_2") (pintype "bidirectional"))
      (node (ref "U$58") (pin "3") (pinfunction "OUTB_3") (pintype "bidirectional"))
    )
    (net (code "39") (name "NEG_PAD16") (class "Default")
      (node (ref "U$61") (pin "P$1") (pinfunction "0_P$1") (pintype "bidirectional"))
      (node (ref "U$62") (pin "1") (pinfunction "OUTR_1") (pintype "bidirectional"))
      (node (ref "U$62") (pin "2") (pinfunction "OUTG_2") (pintype "bidirectional"))
      (node (ref "U$62") (pin "3") (pinfunction "OUTB_3") (pintype "bidirectional"))
    )
    (net (code "40") (name "NEG_PAD17") (class "Default")
      (node (ref "U$65") (pin "P$1") (pinfunction "0_P$1") (pintype "bidirectional"))
      (node (ref "U$66") (pin "1") (pinfunction "OUTR_1") (pintype "bidirectional"))
      (node (ref "U$66") (pin "2") (pinfunction "OUTG_2") (pintype "bidirectional"))
      (node (ref "U$66") (pin "3") (pinfunction "OUTB_3") (pintype "bidirectional"))
    )
    (net (code "41") (name "NEG_PAD18") (class "Default")
      (node (ref "U$69") (pin "P$1") (pinfunction "0_P$1") (pintype "bidirectional"))
      (node (ref "U$70") (pin "1") (pinfunction "OUTR_1") (pintype "bidirectional"))
      (node (ref "U$70") (pin "2") (pinfunction "OUTG_2") (pintype "bidirectional"))
      (node (ref "U$70") (pin "3") (pinfunction "OUTB_3") (pintype "bidirectional"))
    )
    (net (code "42") (name "NEG_PAD19") (class "Default")
      (node (ref "U$73") (pin "P$1") (pinfunction "0_P$1") (pintype "bidirectional"))
      (node (ref "U$74") (pin "1") (pinfunction "OUTR_1") (pintype "bidirectional"))
      (node (ref "U$74") (pin "2") (pinfunction "OUTG_2") (pintype "bidirectional"))
      (node (ref "U$74") (pin "3") (pinfunction "OUTB_3") (pintype "bidirectional"))
    )
    (net (code "43") (name "NEG_PAD20") (class "Default")
      (node (ref "U$77") (pin "P$1") (pinfunction "0_P$1") (pintype "bidirectional"))
      (node (ref "U$78") (pin "1") (pinfunction "OUTR_1") (pintype "bidirectional"))
      (node (ref "U$78") (pin "2") (pinfunction "OUTG_2") (pintype "bidirectional"))
      (node (ref "U$78") (pin "3") (pinfunction "OUTB_3") (pintype "bidirectional"))
    )
    (net (code "44") (name "Net-(U$2-DIN)") (class "Default")
      (node (ref "R4") (pin "1") (pinfunction "1_1") (pintype "passive"))
      (node (ref "U$2") (pin "5") (pinfunction "DIN_5") (pintype "bidirectional"))
    )
    (net (code "45") (name "Net-(U$2-DO)") (class "Default")
      (node (ref "R5") (pin "2") (pinfunction "2_2") (pintype "passive"))
      (node (ref "U$2") (pin "4") (pinfunction "DO_4") (pintype "bidirectional"))
    )
    (net (code "46") (name "Net-(U$2-VDD)") (class "Default")
      (node (ref "R6") (pin "1") (pinfunction "1_1") (pintype "passive"))
      (node (ref "U$2") (pin "8") (pinfunction "VDD_8") (pintype "bidirectional"))
    )
    (net (code "47") (name "Net-(U$6-DIN)") (class "Default")
      (node (ref "R1") (pin "1") (pinfunction "1_1") (pintype "passive"))
      (node (ref "U$6") (pin "5") (pinfunction "DIN_5") (pintype "bidirectional"))
    )
    (net (code "48") (name "Net-(U$6-DO)") (class "Default")
      (node (ref "R2") (pin "2") (pinfunction "2_2") (pintype "passive"))
      (node (ref "U$6") (pin "4") (pinfunction "DO_4") (pintype "bidirectional"))
    )
    (net (code "49") (name "Net-(U$6-VDD)") (class "Default")
      (node (ref "R3") (pin "1") (pinfunction "1_1") (pintype "passive"))
      (node (ref "U$6") (pin "8") (pinfunction "VDD_8") (pintype "bidirectional"))
    )
    (net (code "50") (name "Net-(U$10-DIN)") (class "Default")
      (node (ref "R7") (pin "1") (pinfunction "1_1") (pintype "passive"))
      (node (ref "U$10") (pin "5") (pinfunction "DIN_5") (pintype "bidirectional"))
    )
    (net (code "51") (name "Net-(U$10-DO)") (class "Default")
      (node (ref "R8") (pin "2") (pinfunction "2_2") (pintype "passive"))
      (node (ref "U$10") (pin "4") (pinfunction "DO_4") (pintype "bidirectional"))
    )
    (net (code "52") (name "Net-(U$10-VDD)") (class "Default")
      (node (ref "R9") (pin "1") (pinfunction "1_1") (pintype "passive"))
      (node (ref "U$10") (pin "8") (pinfunction "VDD_8") (pintype "bidirectional"))
    )
    (net (code "53") (name "Net-(U$14-DIN)") (class "Default")
      (node (ref "R10") (pin "1") (pinfunction "1_1") (pintype "passive"))
      (node (ref "U$14") (pin "5") (pinfunction "DIN_5") (pintype "bidirectional"))
    )
    (net (code "54") (name "Net-(U$14-DO)") (class "Default")
      (node (ref "R11") (pin "2") (pinfunction "2_2") (pintype "passive"))
      (node (ref "U$14") (pin "4") (pinfunction "DO_4") (pintype "bidirectional"))
    )
    (net (code "55") (name "Net-(U$14-VDD)") (class "Default")
      (node (ref "R12") (pin "1") (pinfunction "1_1") (pintype "passive"))
      (node (ref "U$14") (pin "8") (pinfunction "VDD_8") (pintype "bidirectional"))
    )
    (net (code "56") (name "Net-(U$18-DIN)") (class "Default")
      (node (ref "R13") (pin "1") (pinfunction "1_1") (pintype "passive"))
      (node (ref "U$18") (pin "5") (pinfunction "DIN_5") (pintype "bidirectional"))
    )
    (net (code "57") (name "Net-(U$18-DO)") (class "Default")
      (node (ref "R14") (pin "2") (pinfunction "2_2") (pintype "passive"))
      (node (ref "U$18") (pin "4") (pinfunction "DO_4") (pintype "bidirectional"))
    )
    (net (code "58") (name "Net-(U$18-VDD)") (class "Default")
      (node (ref "R15") (pin "1") (pinfunction "1_1") (pintype "passive"))
      (node (ref "U$18") (pin "8") (pinfunction "VDD_8") (pintype "bidirectional"))
    )
    (net (code "59") (name "Net-(U$22-DIN)") (class "Default")
      (node (ref "R16") (pin "1") (pinfunction "1_1") (pintype "passive"))
      (node (ref "U$22") (pin "5") (pinfunction "DIN_5") (pintype "bidirectional"))
    )
    (net (code "60") (name "Net-(U$22-DO)") (class "Default")
      (node (ref "R17") (pin "2") (pinfunction "2_2") (pintype "passive"))
      (node (ref "U$22") (pin "4") (pinfunction "DO_4") (pintype "bidirectional"))
    )
    (net (code "61") (name "Net-(U$22-VDD)") (class "Default")
      (node (ref "R18") (pin "1") (pinfunction "1_1") (pintype "passive"))
      (node (ref "U$22") (pin "8") (pinfunction "VDD_8") (pintype "bidirectional"))
    )
    (net (code "62") (name "Net-(U$26-DIN)") (class "Default")
      (node (ref "R19") (pin "1") (pinfunction "1_1") (pintype "passive"))
      (node (ref "U$26") (pin "5") (pinfunction "DIN_5") (pintype "bidirectional"))
    )
    (net (code "63") (name "Net-(U$26-DO)") (class "Default")
      (node (ref "R20") (pin "2") (pinfunction "2_2") (pintype "passive"))
      (node (ref "U$26") (pin "4") (pinfunction "DO_4") (pintype "bidirectional"))
    )
    (net (code "64") (name "Net-(U$26-VDD)") (class "Default")
      (node (ref "R21") (pin "1") (pinfunction "1_1") (pintype "passive"))
      (node (ref "U$26") (pin "8") (pinfunction "VDD_8") (pintype "bidirectional"))
    )
    (net (code "65") (name "Net-(U$30-DIN)") (class "Default")
      (node (ref "R22") (pin "1") (pinfunction "1_1") (pintype "passive"))
      (node (ref "U$30") (pin "5") (pinfunction "DIN_5") (pintype "bidirectional"))
    )
    (net (code "66") (name "Net-(U$30-DO)") (class "Default")
      (node (ref "R23") (pin "2") (pinfunction "2_2") (pintype "passive"))
      (node (ref "U$30") (pin "4") (pinfunction "DO_4") (pintype "bidirectional"))
    )
    (net (code "67") (name "Net-(U$30-VDD)") (class "Default")
      (node (ref "R24") (pin "1") (pinfunction "1_1") (pintype "passive"))
      (node (ref "U$30") (pin "8") (pinfunction "VDD_8") (pintype "bidirectional"))
    )
    (net (code "68") (name "Net-(U$34-DIN)") (class "Default")
      (node (ref "R25") (pin "1") (pinfunction "1_1") (pintype "passive"))
      (node (ref "U$34") (pin "5") (pinfunction "DIN_5") (pintype "bidirectional"))
    )
    (net (code "69") (name "Net-(U$34-DO)") (class "Default")
      (node (ref "R26") (pin "2") (pinfunction "2_2") (pintype "passive"))
      (node (ref "U$34") (pin "4") (pinfunction "DO_4") (pintype "bidirectional"))
    )
    (net (code "70") (name "Net-(U$34-VDD)") (class "Default")
      (node (ref "R27") (pin "1") (pinfunction "1_1") (pintype "passive"))
      (node (ref "U$34") (pin "8") (pinfunction "VDD_8") (pintype "bidirectional"))
    )
    (net (code "71") (name "Net-(U$38-DIN)") (class "Default")
      (node (ref "R28") (pin "1") (pinfunction "1_1") (pintype "passive"))
      (node (ref "U$38") (pin "5") (pinfunction "DIN_5") (pintype "bidirectional"))
    )
    (net (code "72") (name "Net-(U$38-DO)") (class "Default")
      (node (ref "R29") (pin "2") (pinfunction "2_2") (pintype "passive"))
      (node (ref "U$38") (pin "4") (pinfunction "DO_4") (pintype "bidirectional"))
    )
    (net (code "73") (name "Net-(U$38-VDD)") (class "Default")
      (node (ref "R30") (pin "1") (pinfunction "1_1") (pintype "passive"))
      (node (ref "U$38") (pin "8") (pinfunction "VDD_8") (pintype "bidirectional"))
    )
    (net (code "74") (name "Net-(U$42-DIN)") (class "Default")
      (node (ref "R31") (pin "1") (pinfunction "1_1") (pintype "passive"))
      (node (ref "U$42") (pin "5") (pinfunction "DIN_5") (pintype "bidirectional"))
    )
    (net (code "75") (name "Net-(U$42-DO)") (class "Default")
      (node (ref "R32") (pin "2") (pinfunction "2_2") (pintype "passive"))
      (node (ref "U$42") (pin "4") (pinfunction "DO_4") (pintype "bidirectional"))
    )
    (net (code "76") (name "Net-(U$42-VDD)") (class "Default")
      (node (ref "R33") (pin "1") (pinfunction "1_1") (pintype "passive"))
      (node (ref "U$42") (pin "8") (pinfunction "VDD_8") (pintype "bidirectional"))
    )
    (net (code "77") (name "Net-(U$46-DIN)") (class "Default")
      (node (ref "R34") (pin "1") (pinfunction "1_1") (pintype "passive"))
      (node (ref "U$46") (pin "5") (pinfunction "DIN_5") (pintype "bidirectional"))
    )
    (net (code "78") (name "Net-(U$46-DO)") (class "Default")
      (node (ref "R35") (pin "2") (pinfunction "2_2") (pintype "passive"))
      (node (ref "U$46") (pin "4") (pinfunction "DO_4") (pintype "bidirectional"))
    )
    (net (code "79") (name "Net-(U$46-VDD)") (class "Default")
      (node (ref "R36") (pin "1") (pinfunction "1_1") (pintype "passive"))
      (node (ref "U$46") (pin "8") (pinfunction "VDD_8") (pintype "bidirectional"))
    )
    (net (code "80") (name "Net-(U$50-DIN)") (class "Default")
      (node (ref "R37") (pin "1") (pinfunction "1_1") (pintype "passive"))
      (node (ref "U$50") (pin "5") (pinfunction "DIN_5") (pintype "bidirectional"))
    )
    (net (code "81") (name "Net-(U$50-DO)") (class "Default")
      (node (ref "R38") (pin "2") (pinfunction "2_2") (pintype "passive"))
      (node (ref "U$50") (pin "4") (pinfunction "DO_4") (pintype "bidirectional"))
    )
    (net (code "82") (name "Net-(U$50-VDD)") (class "Default")
      (node (ref "R39") (pin "1") (pinfunction "1_1") (pintype "passive"))
      (node (ref "U$50") (pin "8") (pinfunction "VDD_8") (pintype "bidirectional"))
    )
    (net (code "83") (name "Net-(U$54-DIN)") (class "Default")
      (node (ref "R40") (pin "1") (pinfunction "1_1") (pintype "passive"))
      (node (ref "U$54") (pin "5") (pinfunction "DIN_5") (pintype "bidirectional"))
    )
    (net (code "84") (name "Net-(U$54-DO)") (class "Default")
      (node (ref "R41") (pin "2") (pinfunction "2_2") (pintype "passive"))
      (node (ref "U$54") (pin "4") (pinfunction "DO_4") (pintype "bidirectional"))
    )
    (net (code "85") (name "Net-(U$54-VDD)") (class "Default")
      (node (ref "R42") (pin "1") (pinfunction "1_1") (pintype "passive"))
      (node (ref "U$54") (pin "8") (pinfunction "VDD_8") (pintype "bidirectional"))
    )
    (net (code "86") (name "Net-(U$58-DIN)") (class "Default")
      (node (ref "R43") (pin "1") (pinfunction "1_1") (pintype "passive"))
      (node (ref "U$58") (pin "5") (pinfunction "DIN_5") (pintype "bidirectional"))
    )
    (net (code "87") (name "Net-(U$58-DO)") (class "Default")
      (node (ref "R44") (pin "2") (pinfunction "2_2") (pintype "passive"))
      (node (ref "U$58") (pin "4") (pinfunction "DO_4") (pintype "bidirectional"))
    )
    (net (code "88") (name "Net-(U$58-VDD)") (class "Default")
      (node (ref "R45") (pin "1") (pinfunction "1_1") (pintype "passive"))
      (node (ref "U$58") (pin "8") (pinfunction "VDD_8") (pintype "bidirectional"))
    )
    (net (code "89") (name "Net-(U$62-DIN)") (class "Default")
      (node (ref "R46") (pin "1") (pinfunction "1_1") (pintype "passive"))
      (node (ref "U$62") (pin "5") (pinfunction "DIN_5") (pintype "bidirectional"))
    )
    (net (code "90") (name "Net-(U$62-DO)") (class "Default")
      (node (ref "R47") (pin "2") (pinfunction "2_2") (pintype "passive"))
      (node (ref "U$62") (pin "4") (pinfunction "DO_4") (pintype "bidirectional"))
    )
    (net (code "91") (name "Net-(U$62-VDD)") (class "Default")
      (node (ref "R48") (pin "1") (pinfunction "1_1") (pintype "passive"))
      (node (ref "U$62") (pin "8") (pinfunction "VDD_8") (pintype "bidirectional"))
    )
    (net (code "92") (name "Net-(U$66-DIN)") (class "Default")
      (node (ref "R49") (pin "1") (pinfunction "1_1") (pintype "passive"))
      (node (ref "U$66") (pin "5") (pinfunction "DIN_5") (pintype "bidirectional"))
    )
    (net (code "93") (name "Net-(U$66-DO)") (class "Default")
      (node (ref "R50") (pin "2") (pinfunction "2_2") (pintype "passive"))
      (node (ref "U$66") (pin "4") (pinfunction "DO_4") (pintype "bidirectional"))
    )
    (net (code "94") (name "Net-(U$66-VDD)") (class "Default")
      (node (ref "R51") (pin "1") (pinfunction "1_1") (pintype "passive"))
      (node (ref "U$66") (pin "8") (pinfunction "VDD_8") (pintype "bidirectional"))
    )
    (net (code "95") (name "Net-(U$70-DIN)") (class "Default")
      (node (ref "R52") (pin "1") (pinfunction "1_1") (pintype "passive"))
      (node (ref "U$70") (pin "5") (pinfunction "DIN_5") (pintype "bidirectional"))
    )
    (net (code "96") (name "Net-(U$70-DO)") (class "Default")
      (node (ref "R53") (pin "2") (pinfunction "2_2") (pintype "passive"))
      (node (ref "U$70") (pin "4") (pinfunction "DO_4") (pintype "bidirectional"))
    )
    (net (code "97") (name "Net-(U$70-VDD)") (class "Default")
      (node (ref "R54") (pin "1") (pinfunction "1_1") (pintype "passive"))
      (node (ref "U$70") (pin "8") (pinfunction "VDD_8") (pintype "bidirectional"))
    )
    (net (code "98") (name "Net-(U$74-DIN)") (class "Default")
      (node (ref "R55") (pin "1") (pinfunction "1_1") (pintype "passive"))
      (node (ref "U$74") (pin "5") (pinfunction "DIN_5") (pintype "bidirectional"))
    )
    (net (code "99") (name "Net-(U$74-DO)") (class "Default")
      (node (ref "R56") (pin "2") (pinfunction "2_2") (pintype "passive"))
      (node (ref "U$74") (pin "4") (pinfunction "DO_4") (pintype "bidirectional"))
    )
    (net (code "100") (name "Net-(U$74-VDD)") (class "Default")
      (node (ref "R57") (pin "1") (pinfunction "1_1") (pintype "passive"))
      (node (ref "U$74") (pin "8") (pinfunction "VDD_8") (pintype "bidirectional"))
    )
    (net (code "101") (name "Net-(U$78-DIN)") (class "Default")
      (node (ref "R58") (pin "1") (pinfunction "1_1") (pintype "passive"))
      (node (ref "U$78") (pin "5") (pinfunction "DIN_5") (pintype "bidirectional"))
    )
    (net (code "102") (name "Net-(U$78-DO)") (class "Default")
      (node (ref "R59") (pin "2") (pinfunction "2_2") (pintype "passive"))
      (node (ref "U$78") (pin "4") (pinfunction "DO_4") (pintype "bidirectional"))
    )
    (net (code "103") (name "Net-(U$78-VDD)") (class "Default")
      (node (ref "R60") (pin "1") (pinfunction "1_1") (pintype "passive"))
      (node (ref "U$78") (pin "8") (pinfunction "VDD_8") (pintype "bidirectional"))
    )
    (net (code "104") (name "VCC") (class "Default")
      (node (ref "C1") (pin "1") (pinfunction "1_1") (pintype "passive"))
      (node (ref "C10") (pin "1") (pinfunction "1_1") (pintype "passive"))
      (node (ref "C11") (pin "1") (pinfunction "1_1") (pintype "passive"))
      (node (ref "C12") (pin "1") (pinfunction "1_1") (pintype "passive"))
      (node (ref "C13") (pin "1") (pinfunction "1_1") (pintype "passive"))
      (node (ref "C14") (pin "1") (pinfunction "1_1") (pintype "passive"))
      (node (ref "C15") (pin "1") (pinfunction "1_1") (pintype "passive"))
      (node (ref "C16") (pin "1") (pinfunction "1_1") (pintype "passive"))
      (node (ref "C17") (pin "1") (pinfunction "1_1") (pintype "passive"))
      (node (ref "C18") (pin "1") (pinfunction "1_1") (pintype "passive"))
      (node (ref "C19") (pin "1") (pinfunction "1_1") (pintype "passive"))
      (node (ref "C2") (pin "1") (pinfunction "1_1") (pintype "passive"))
      (node (ref "C20") (pin "1") (pinfunction "1_1") (pintype "passive"))
      (node (ref "C3") (pin "1") (pinfunction "1_1") (pintype "passive"))
      (node (ref "C4") (pin "1") (pinfunction "1_1") (pintype "passive"))
      (node (ref "C5") (pin "1") (pinfunction "1_1") (pintype "passive"))
      (node (ref "C6") (pin "1") (pinfunction "1_1") (pintype "passive"))
      (node (ref "C7") (pin "1") (pinfunction "1_1") (pintype "passive"))
      (node (ref "C8") (pin "1") (pinfunction "1_1") (pintype "passive"))
      (node (ref "C9") (pin "1") (pinfunction "1_1") (pintype "passive"))
      (node (ref "IN1") (pin "4") (pinfunction "VCC_4") (pintype "bidirectional"))
      (node (ref "OUT1") (pin "4") (pinfunction "VCC_4") (pintype "bidirectional"))
      (node (ref "R12") (pin "2") (pinfunction "2_2") (pintype "passive"))
      (node (ref "R15") (pin "2") (pinfunction "2_2") (pintype "passive"))
      (node (ref "R18") (pin "2") (pinfunction "2_2") (pintype "passive"))
      (node (ref "R21") (pin "2") (pinfunction "2_2") (pintype "passive"))
      (node (ref "R24") (pin "2") (pinfunction "2_2") (pintype "passive"))
      (node (ref "R27") (pin "2") (pinfunction "2_2") (pintype "passive"))
      (node (ref "R3") (pin "2") (pinfunction "2_2") (pintype "passive"))
      (node (ref "R30") (pin "2") (pinfunction "2_2") (pintype "passive"))
      (node (ref "R33") (pin "2") (pinfunction "2_2") (pintype "passive"))
      (node (ref "R36") (pin "2") (pinfunction "2_2") (pintype "passive"))
      (node (ref "R39") (pin "2") (pinfunction "2_2") (pintype "passive"))
      (node (ref "R42") (pin "2") (pinfunction "2_2") (pintype "passive"))
      (node (ref "R45") (pin "2") (pinfunction "2_2") (pintype "passive"))
      (node (ref "R48") (pin "2") (pinfunction "2_2") (pintype "passive"))
      (node (ref "R51") (pin "2") (pinfunction "2_2") (pintype "passive"))
      (node (ref "R54") (pin "2") (pinfunction "2_2") (pintype "passive"))
      (node (ref "R57") (pin "2") (pinfunction "2_2") (pintype "passive"))
      (node (ref "R6") (pin "2") (pinfunction "2_2") (pintype "passive"))
      (node (ref "R60") (pin "2") (pinfunction "2_2") (pintype "passive"))
      (node (ref "R9") (pin "2") (pinfunction "2_2") (pintype "passive"))
      (node (ref "U$1") (pin "P$2") (pinfunction "1_P$2") (pintype "bidirectional"))
      (node (ref "U$11") (pin "4") (pinfunction "VCC_4") (pintype "bidirectional"))
      (node (ref "U$12") (pin "4") (pinfunction "VCC_4") (pintype "bidirectional"))
      (node (ref "U$13") (pin "P$2") (pinfunction "1_P$2") (pintype "bidirectional"))
      (node (ref "U$15") (pin "4") (pinfunction "VCC_4") (pintype "bidirectional"))
      (node (ref "U$16") (pin "4") (pinfunction "VCC_4") (pintype "bidirectional"))
      (node (ref "U$17") (pin "P$2") (pinfunction "1_P$2") (pintype "bidirectional"))
      (node (ref "U$19") (pin "4") (pinfunction "VCC_4") (pintype "bidirectional"))
      (node (ref "U$20") (pin "4") (pinfunction "VCC_4") (pintype "bidirectional"))
      (node (ref "U$21") (pin "P$2") (pinfunction "1_P$2") (pintype "bidirectional"))
      (node (ref "U$23") (pin "4") (pinfunction "VCC_4") (pintype "bidirectional"))
      (node (ref "U$24") (pin "4") (pinfunction "VCC_4") (pintype "bidirectional"))
      (node (ref "U$25") (pin "P$2") (pinfunction "1_P$2") (pintype "bidirectional"))
      (node (ref "U$27") (pin "4") (pinfunction "VCC_4") (pintype "bidirectional"))
      (node (ref "U$28") (pin "4") (pinfunction "VCC_4") (pintype "bidirectional"))
      (node (ref "U$29") (pin "P$2") (pinfunction "1_P$2") (pintype "bidirectional"))
      (node (ref "U$31") (pin "4") (pinfunction "VCC_4") (pintype "bidirectional"))
      (node (ref "U$32") (pin "4") (pinfunction "VCC_4") (pintype "bidirectional"))
      (node (ref "U$33") (pin "P$2") (pinfunction "1_P$2") (pintype "bidirectional"))
      (node (ref "U$35") (pin "4") (pinfunction "VCC_4") (pintype "bidirectional"))
      (node (ref "U$36") (pin "4") (pinfunction "VCC_4") (pintype "bidirectional"))
      (node (ref "U$37") (pin "P$2") (pinfunction "1_P$2") (pintype "bidirectional"))
      (node (ref "U$39") (pin "4") (pinfunction "VCC_4") (pintype "bidirectional"))
      (node (ref "U$40") (pin "4") (pinfunction "VCC_4") (pintype "bidirectional"))
      (node (ref "U$41") (pin "P$2") (pinfunction "1_P$2") (pintype "bidirectional"))
      (node (ref "U$43") (pin "4") (pinfunction "VCC_4") (pintype "bidirectional"))
      (node (ref "U$44") (pin "4") (pinfunction "VCC_4") (pintype "bidirectional"))
      (node (ref "U$45") (pin "P$2") (pinfunction "1_P$2") (pintype "bidirectional"))
      (node (ref "U$47") (pin "4") (pinfunction "VCC_4") (pintype "bidirectional"))
      (node (ref "U$48") (pin "4") (pinfunction "VCC_4") (pintype "bidirectional"))
      (node (ref "U$49") (pin "P$2") (pinfunction "1_P$2") (pintype "bidirectional"))
      (node (ref "U$5") (pin "P$2") (pinfunction "1_P$2") (pintype "bidirectional"))
      (node (ref "U$51") (pin "4") (pinfunction "VCC_4") (pintype "bidirectional"))
      (node (ref "U$52") (pin "4") (pinfunction "VCC_4") (pintype "bidirectional"))
      (node (ref "U$53") (pin "P$2") (pinfunction "1_P$2") (pintype "bidirectional"))
      (node (ref "U$55") (pin "4") (pinfunction "VCC_4") (pintype "bidirectional"))
      (node (ref "U$56") (pin "4") (pinfunction "VCC_4") (pintype "bidirectional"))
      (node (ref "U$57") (pin "P$2") (pinfunction "1_P$2") (pintype "bidirectional"))
      (node (ref "U$59") (pin "4") (pinfunction "VCC_4") (pintype "bidirectional"))
      (node (ref "U$60") (pin "4") (pinfunction "VCC_4") (pintype "bidirectional"))
      (node (ref "U$61") (pin "P$2") (pinfunction "1_P$2") (pintype "bidirectional"))
      (node (ref "U$63") (pin "4") (pinfunction "VCC_4") (pintype "bidirectional"))
      (node (ref "U$64") (pin "4") (pinfunction "VCC_4") (pintype "bidirectional"))
      (node (ref "U$65") (pin "P$2") (pinfunction "1_P$2") (pintype "bidirectional"))
      (node (ref "U$67") (pin "4") (pinfunction "VCC_4") (pintype "bidirectional"))
      (node (ref "U$68") (pin "4") (pinfunction "VCC_4") (pintype "bidirectional"))
      (node (ref "U$69") (pin "P$2") (pinfunction "1_P$2") (pintype "bidirectional"))
      (node (ref "U$7") (pin "4") (pinfunction "VCC_4") (pintype "bidirectional"))
      (node (ref "U$71") (pin "4") (pinfunction "VCC_4") (pintype "bidirectional"))
      (node (ref "U$72") (pin "4") (pinfunction "VCC_4") (pintype "bidirectional"))
      (node (ref "U$73") (pin "P$2") (pinfunction "1_P$2") (pintype "bidirectional"))
      (node (ref "U$75") (pin "4") (pinfunction "VCC_4") (pintype "bidirectional"))
      (node (ref "U$76") (pin "4") (pinfunction "VCC_4") (pintype "bidirectional"))
      (node (ref "U$77") (pin "P$2") (pinfunction "1_P$2") (pintype "bidirectional"))
      (node (ref "U$79") (pin "4") (pinfunction "VCC_4") (pintype "bidirectional"))
      (node (ref "U$8") (pin "4") (pinfunction "VCC_4") (pintype "bidirectional"))
      (node (ref "U$80") (pin "4") (pinfunction "VCC_4") (pintype "bidirectional"))
      (node (ref "U$9") (pin "P$2") (pinfunction "1_P$2") (pintype "bidirectional"))
    )
  )
)
